# 3_5_2-_-V3_3-2023_10_27.net
KiCad netlist of a schematic drawn in Altium Designer
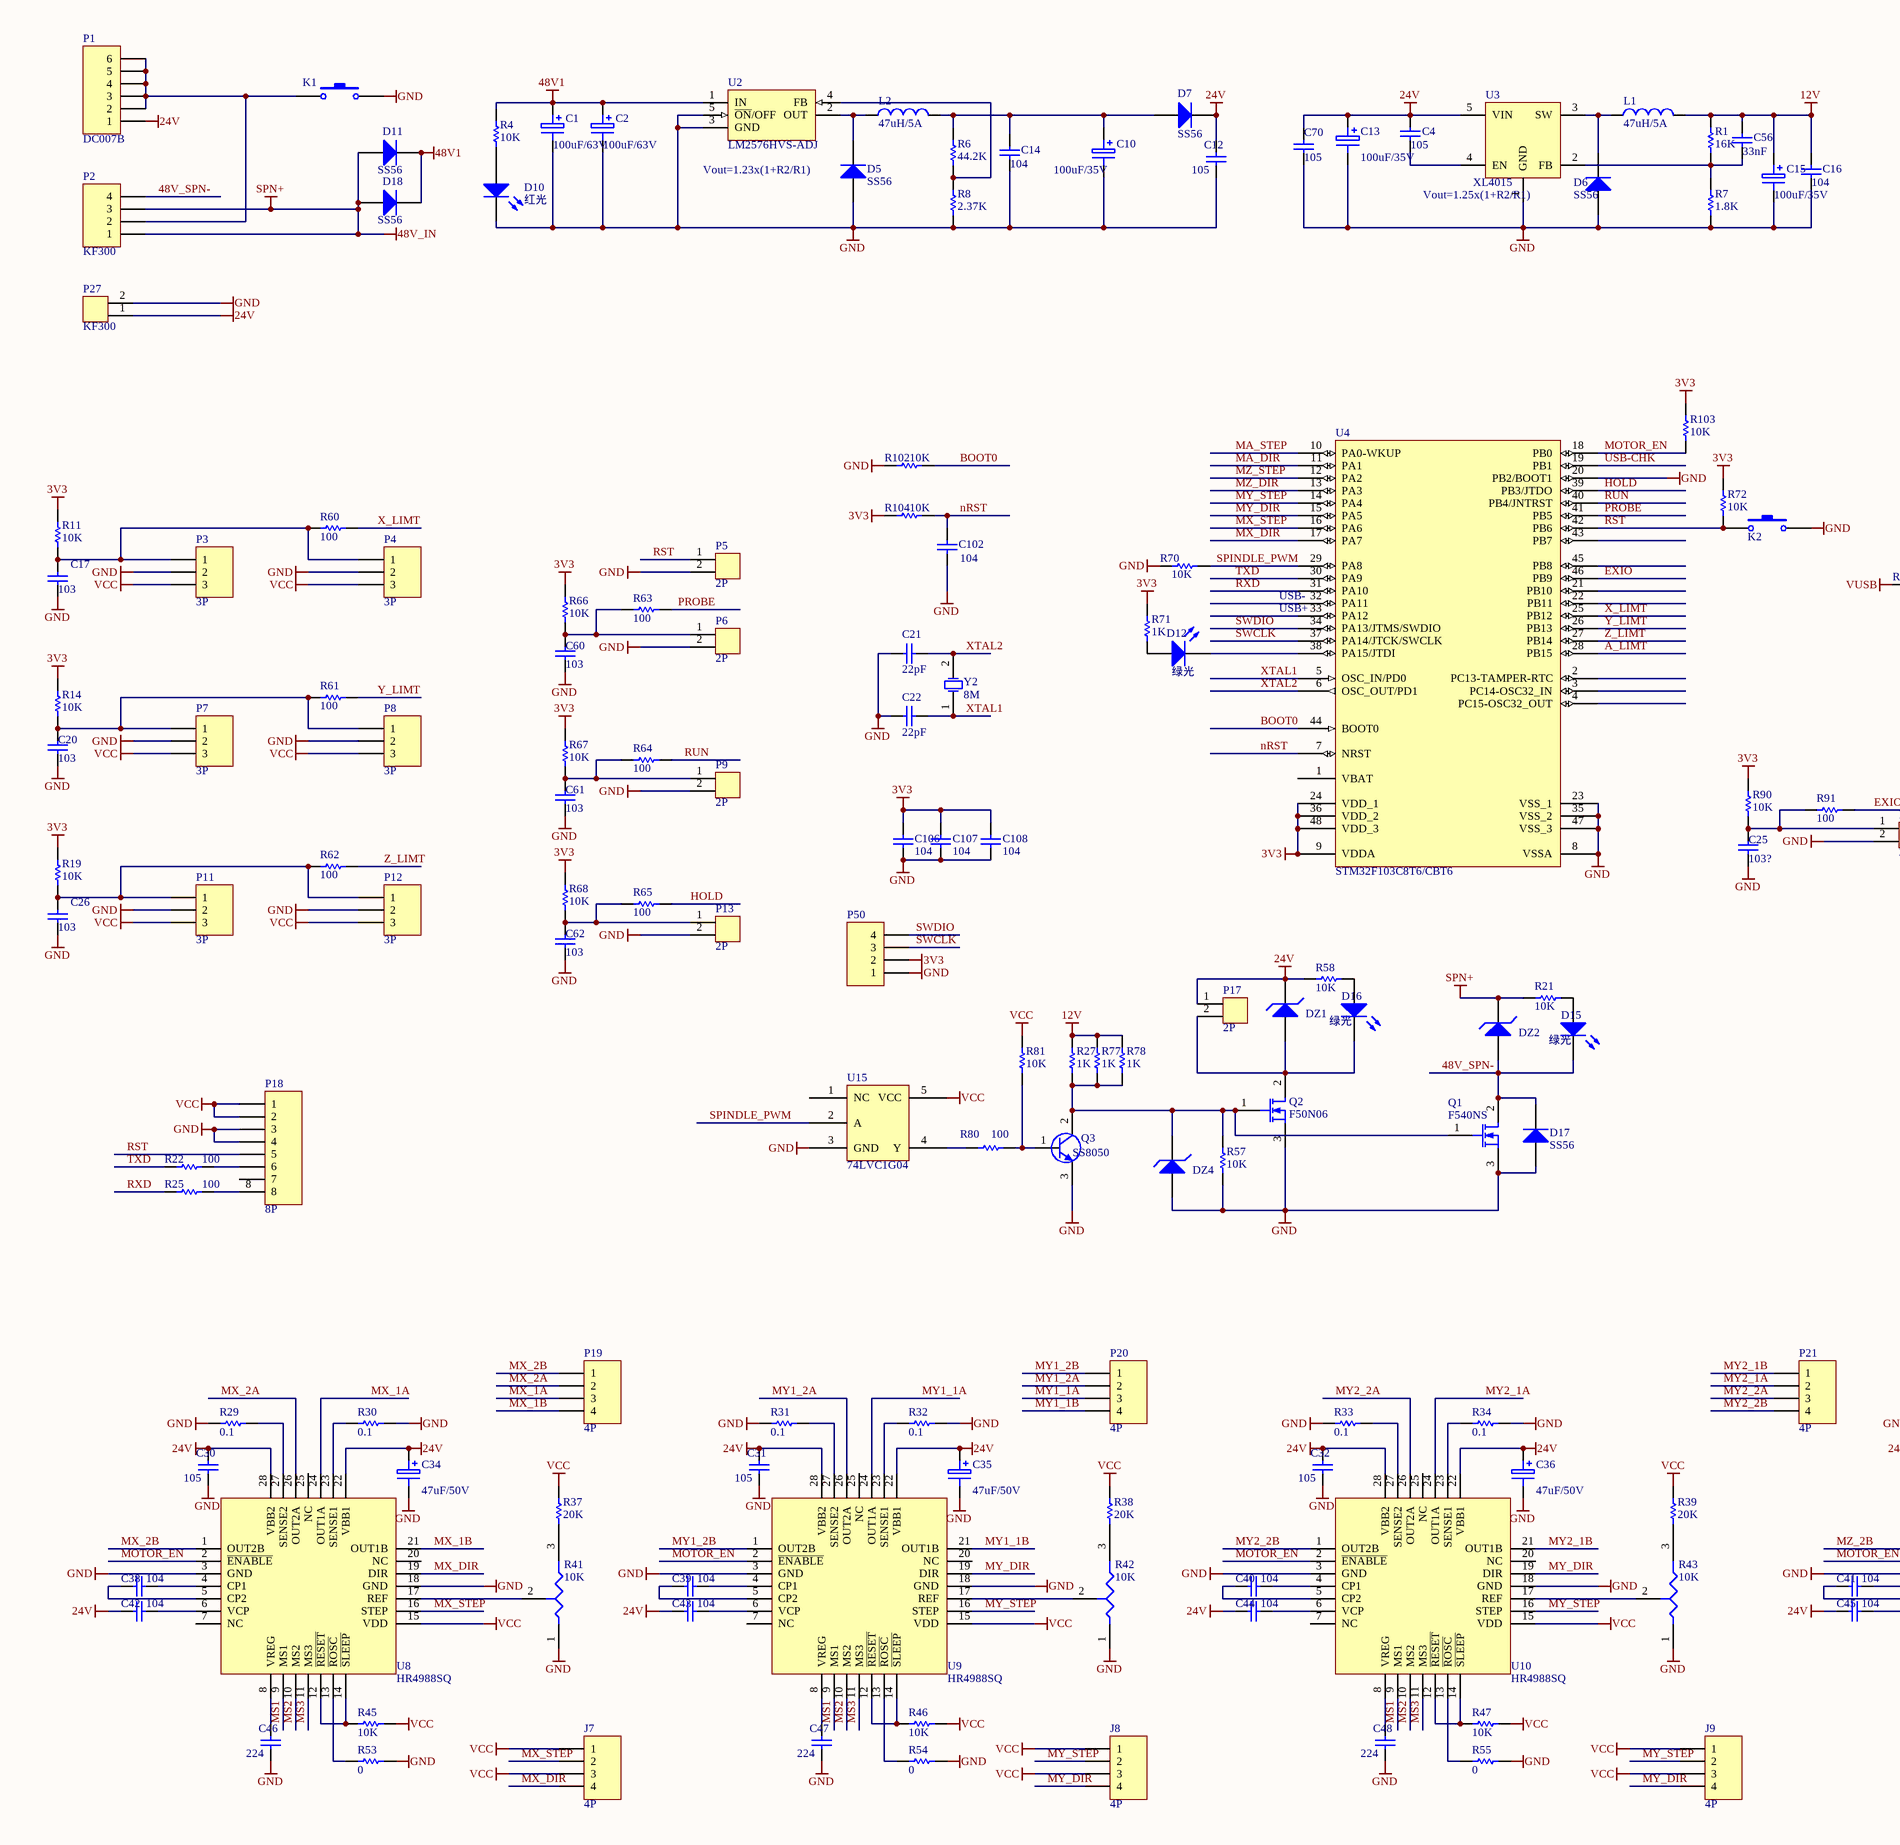
[diagram p0: 3轴5.2-原理图-V3.3-2023.10.27.SchDoc, left]
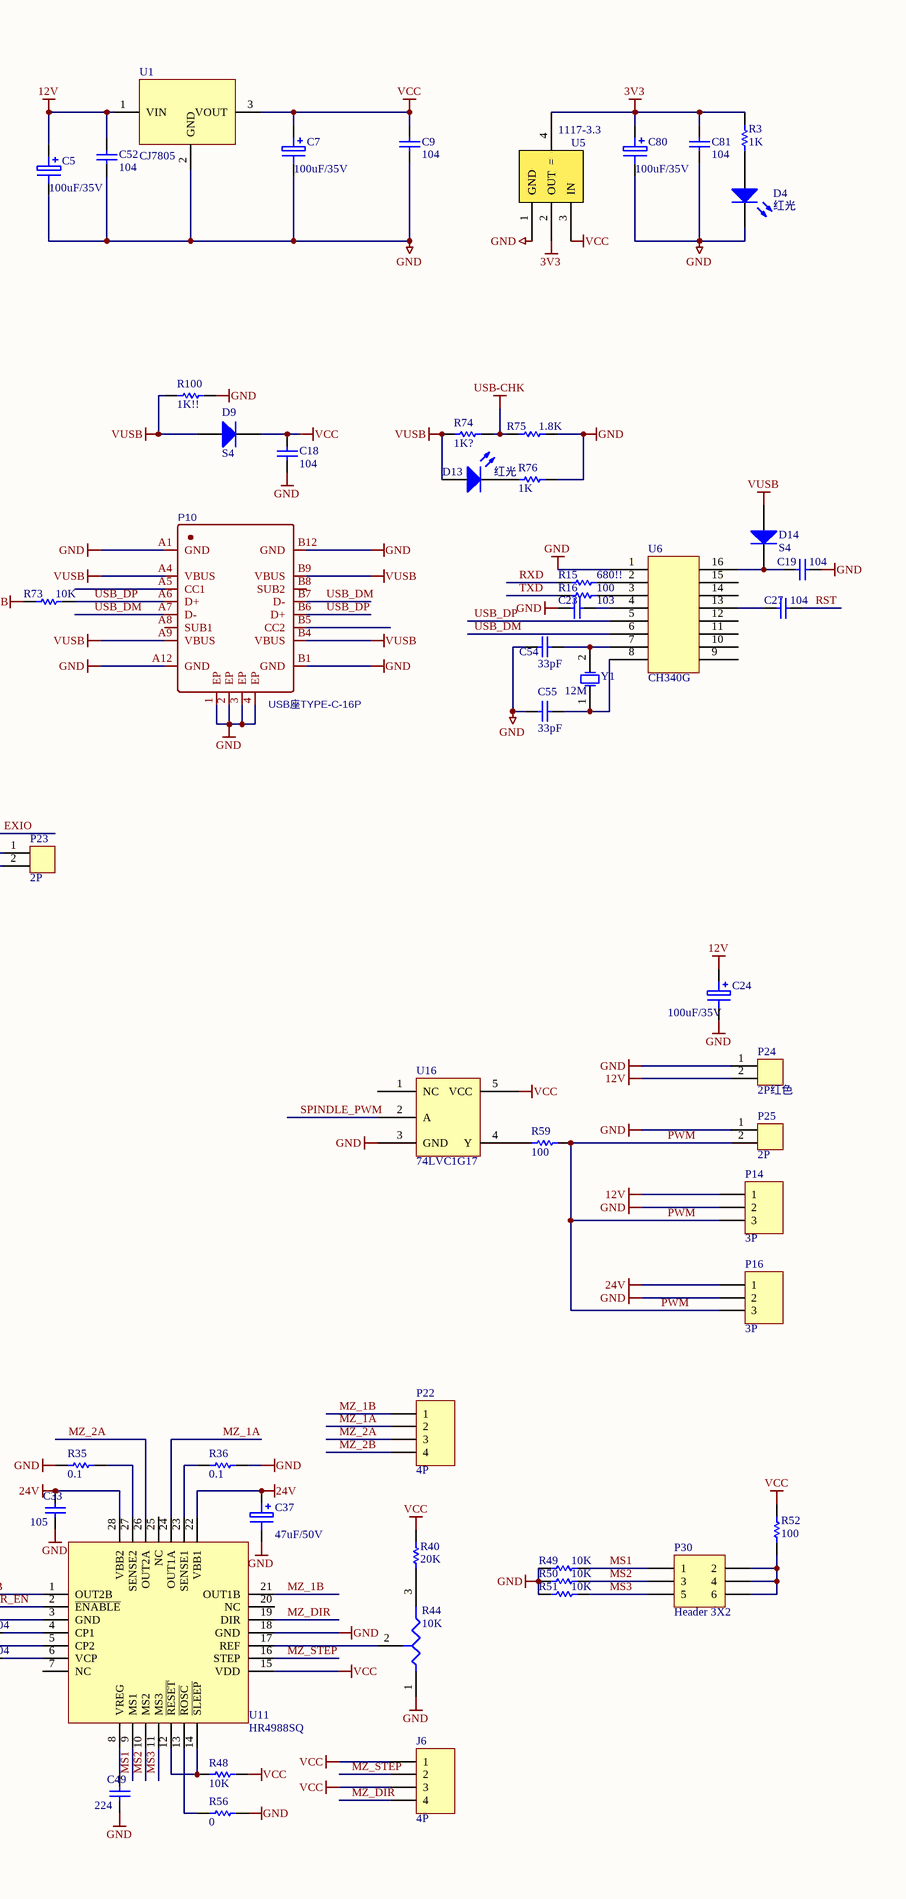
[diagram p1: 3轴5.2-原理图-V3.3-2023.10.27.SchDoc, right]

(export (version "E")
  (design (tool "Eeschema 10.0.6"))
  (components
    (comp (ref "C1") (value "100uF/63V") (footprint "电解电容贴片10x10") (libsource (lib "*") (part "ELECTRO1")))
    (comp (ref "C2") (value "100uF/63V") (footprint "电解电容贴片10x10") (libsource (lib "*") (part "ELECTRO1")))
    (comp (ref "C4") (value "105") (footprint "0805C") (libsource (lib "SCH封装库") (part "CAP")))
    (comp (ref "C5") (value "100uF/35V") (footprint "电解电容贴片6x6") (libsource (lib "*") (part "ELECTRO1")))
    (comp (ref "C7") (value "100uF/35V") (footprint "电解电容贴片6x6") (libsource (lib "*") (part "ELECTRO1")))
    (comp (ref "C9")
      (value "104")
      (footprint "0603C")
      (description "Capacitor (Semiconductor SIM Model)")
      (fields (field (name "PUBLISHER") "Altium Limited"))
      (libsource (lib "Miscellaneous Devices") (part "Cap Semi"))
    )
    (comp (ref "C10") (value "100uF/35V") (footprint "电解电容贴片6x6") (libsource (lib "*") (part "ELECTRO1")))
    (comp (ref "C12") (value "105") (footprint "0805C") (libsource (lib "SCH封装库") (part "CAP")))
    (comp (ref "C13") (value "100uF/35V") (footprint "电解电容贴片6x6") (libsource (lib "*") (part "ELECTRO1")))
    (comp (ref "C14") (value "104") (footprint "0603C") (libsource (lib "SCH封装库") (part "CAP")))
    (comp (ref "C15") (value "100uF/35V") (footprint "电解电容贴片6x6") (libsource (lib "*") (part "ELECTRO1")))
    (comp (ref "C16") (value "104") (footprint "0603C") (libsource (lib "SCH封装库") (part "CAP")))
    (comp (ref "C17") (value "103") (footprint "0603C") (libsource (lib "SCH封装库") (part "CAP")))
    (comp (ref "C18")
      (value "104")
      (footprint "0603C")
      (description "Capacitor (Semiconductor SIM Model)")
      (fields (field (name "PUBLISHER") "Altium Limited"))
      (libsource (lib "Miscellaneous Devices") (part "Cap Semi"))
    )
    (comp (ref "C19")
      (value "104")
      (footprint "0603C")
      (description "Capacitor (Semiconductor SIM Model)")
      (fields (field (name "PUBLISHER") "Altium Limited"))
      (libsource (lib "Miscellaneous Devices") (part "Cap Semi"))
    )
    (comp (ref "C20") (value "103") (footprint "0603C") (libsource (lib "SCH封装库") (part "CAP")))
    (comp (ref "C21")
      (value "22pF")
      (footprint "0603C")
      (description "Capacitor (Semiconductor SIM Model)")
      (fields (field (name "PUBLISHER") "Altium Limited"))
      (libsource (lib "Miscellaneous Devices") (part "Cap Semi"))
    )
    (comp (ref "C22")
      (value "22pF")
      (footprint "0603C")
      (description "Capacitor (Semiconductor SIM Model)")
      (fields (field (name "PUBLISHER") "Altium Limited"))
      (libsource (lib "Miscellaneous Devices") (part "Cap Semi"))
    )
    (comp (ref "C23")
      (value "103")
      (footprint "0603C")
      (description "Capacitor (Semiconductor SIM Model)")
      (fields (field (name "PUBLISHER") "Altium Limited"))
      (libsource (lib "Miscellaneous Devices") (part "Cap Semi"))
    )
    (comp (ref "C24") (value "100uF/35V") (footprint "电解电容贴片6x6") (libsource (lib "*") (part "ELECTRO1")))
    (comp (ref "C25") (value "103?") (footprint "0603C") (libsource (lib "SCH封装库") (part "CAP")))
    (comp (ref "C26") (value "103") (footprint "0603C") (libsource (lib "SCH封装库") (part "CAP")))
    (comp (ref "C27")
      (value "104")
      (footprint "0603C")
      (description "Capacitor (Semiconductor SIM Model)")
      (fields (field (name "PUBLISHER") "Altium Limited"))
      (libsource (lib "Miscellaneous Devices") (part "Cap Semi"))
    )
    (comp (ref "C30") (value "105") (footprint "0805C") (libsource (lib "SCH封装库") (part "CAP")))
    (comp (ref "C31") (value "105") (footprint "0805C") (libsource (lib "SCH封装库") (part "CAP")))
    (comp (ref "C32") (value "105") (footprint "0805C") (libsource (lib "SCH封装库") (part "CAP")))
    (comp (ref "C33") (value "105") (footprint "0805C") (libsource (lib "SCH封装库") (part "CAP")))
    (comp (ref "C34") (value "47uF/50V") (footprint "电解电容贴片6x6") (libsource (lib "*") (part "ELECTRO1")))
    (comp (ref "C35") (value "47uF/50V") (footprint "电解电容贴片6x6") (libsource (lib "*") (part "ELECTRO1")))
    (comp (ref "C36") (value "47uF/50V") (footprint "电解电容贴片6x6") (libsource (lib "*") (part "ELECTRO1")))
    (comp (ref "C37") (value "47uF/50V") (footprint "电解电容贴片6x6") (libsource (lib "*") (part "ELECTRO1")))
    (comp (ref "C38") (value "104") (footprint "0603C") (libsource (lib "SCH封装库") (part "CAP")))
    (comp (ref "C39") (value "104") (footprint "0603C") (libsource (lib "SCH封装库") (part "CAP")))
    (comp (ref "C40") (value "104") (footprint "0603C") (libsource (lib "SCH封装库") (part "CAP")))
    (comp (ref "C41") (value "104") (footprint "0603C") (libsource (lib "SCH封装库") (part "CAP")))
    (comp (ref "C42") (value "104") (footprint "0603C") (libsource (lib "SCH封装库") (part "CAP")))
    (comp (ref "C43") (value "104") (footprint "0603C") (libsource (lib "SCH封装库") (part "CAP")))
    (comp (ref "C44") (value "104") (footprint "0603C") (libsource (lib "SCH封装库") (part "CAP")))
    (comp (ref "C45") (value "104") (footprint "0603C") (libsource (lib "SCH封装库") (part "CAP")))
    (comp (ref "C46") (value "224") (footprint "0603C") (libsource (lib "SCH封装库") (part "CAP")))
    (comp (ref "C47") (value "224") (footprint "0603C") (libsource (lib "SCH封装库") (part "CAP")))
    (comp (ref "C48") (value "224") (footprint "0603C") (libsource (lib "SCH封装库") (part "CAP")))
    (comp (ref "C49") (value "224") (footprint "0603C") (libsource (lib "SCH封装库") (part "CAP")))
    (comp (ref "C52")
      (value "104")
      (footprint "0603C")
      (description "Capacitor (Semiconductor SIM Model)")
      (fields (field (name "PUBLISHER") "Altium Limited"))
      (libsource (lib "Miscellaneous Devices") (part "Cap Semi"))
    )
    (comp (ref "C54")
      (value "33pF")
      (footprint "0603C")
      (description "Capacitor (Semiconductor SIM Model)")
      (fields (field (name "PUBLISHER") "Altium Limited"))
      (libsource (lib "Miscellaneous Devices") (part "Cap Semi"))
    )
    (comp (ref "C55")
      (value "33pF")
      (footprint "0603C")
      (description "Capacitor (Semiconductor SIM Model)")
      (fields (field (name "PUBLISHER") "Altium Limited"))
      (libsource (lib "Miscellaneous Devices") (part "Cap Semi"))
    )
    (comp (ref "C56") (value "33nF") (footprint "0603C") (libsource (lib "SCH封装库") (part "CAP")))
    (comp (ref "C60") (value "103") (footprint "0603C") (libsource (lib "SCH封装库") (part "CAP")))
    (comp (ref "C61") (value "103") (footprint "0603C") (libsource (lib "SCH封装库") (part "CAP")))
    (comp (ref "C62") (value "103") (footprint "0603C") (libsource (lib "SCH封装库") (part "CAP")))
    (comp (ref "C70") (value "105") (footprint "0805C") (libsource (lib "SCH封装库") (part "CAP")))
    (comp (ref "C80") (value "100uF/35V") (footprint "电解电容贴片6x6") (libsource (lib "*") (part "ELECTRO1")))
    (comp (ref "C81")
      (value "104")
      (footprint "0603C")
      (description "Capacitor (Semiconductor SIM Model)")
      (fields (field (name "PUBLISHER") "Altium Limited"))
      (libsource (lib "Miscellaneous Devices") (part "Cap Semi"))
    )
    (comp (ref "C102")
      (value "104")
      (footprint "0603C")
      (description "Capacitor (Semiconductor SIM Model)")
      (fields (field (name "PUBLISHER") "Altium Limited"))
      (libsource (lib "Miscellaneous Devices") (part "Cap Semi"))
    )
    (comp (ref "C106") (value "104") (footprint "0603C") (libsource (lib "SCH封装库") (part "CAP")))
    (comp (ref "C107") (value "104") (footprint "0603C") (libsource (lib "SCH封装库") (part "CAP")))
    (comp (ref "C108") (value "104") (footprint "0603C") (libsource (lib "SCH封装库") (part "CAP")))
    (comp (ref "D4") (value "红光") (footprint "0603LED") (libsource (lib "SCH封装库") (part "LED")))
    (comp (ref "D5") (value "SS56") (footprint "SMA") (libsource (lib "SCH封装库") (part "1N4148")))
    (comp (ref "D6") (value "SS56") (footprint "SMA") (libsource (lib "SCH封装库") (part "1N4148")))
    (comp (ref "D7") (value "SS56") (footprint "SMA") (libsource (lib "SCH封装库") (part "1N4148")))
    (comp (ref "D9") (value "S4") (footprint "SOD-123") (libsource (lib "SCH封装库") (part "1N4148")))
    (comp (ref "D10") (value "红光") (footprint "0603LED") (libsource (lib "SCH封装库") (part "LED")))
    (comp (ref "D11") (value "SS56") (footprint "SMA") (libsource (lib "SCH封装库") (part "1N4148")))
    (comp (ref "D12") (value "绿光") (footprint "0603LED") (libsource (lib "SCH封装库") (part "LED")))
    (comp (ref "D13") (value "红光") (footprint "0603LED") (libsource (lib "SCH封装库") (part "LED")))
    (comp (ref "D14") (value "S4") (footprint "SOD-123") (libsource (lib "SCH封装库") (part "1N4148")))
    (comp (ref "D15") (value "绿光") (footprint "0603LED") (libsource (lib "SCH封装库") (part "LED")))
    (comp (ref "D16") (value "绿光") (footprint "0603LED") (libsource (lib "SCH封装库") (part "LED")))
    (comp (ref "D17") (value "SS56") (footprint "SMA") (libsource (lib "SCH封装库") (part "1N4148")))
    (comp (ref "D18") (value "SS56") (footprint "SMA") (libsource (lib "SCH封装库") (part "1N4148")))
    (comp (ref "DZ1") (value "快恢复二极管RS2M") (footprint "SMC") (libsource (lib "SCH封装库") (part "稳压二极管")))
    (comp (ref "DZ2") (value "快恢复二极管RS2M") (footprint "SMC") (libsource (lib "SCH封装库") (part "稳压二极管")))
    (comp (ref "DZ4") (value "稳压二极管SMAZ10V") (footprint "SMA") (libsource (lib "SCH封装库") (part "稳压二极管")))
    (comp (ref "J6") (value "4P") (footprint "SIP4") (libsource (lib "SCH封装库") (part "4P")))
    (comp (ref "J7") (value "4P") (footprint "SIP4") (libsource (lib "SCH封装库") (part "4P")))
    (comp (ref "J8") (value "4P") (footprint "SIP4") (libsource (lib "SCH封装库") (part "4P")))
    (comp (ref "J9") (value "4P") (footprint "SIP4") (libsource (lib "SCH封装库") (part "4P")))
    (comp (ref "K1") (value "按键") (footprint "船型开关KCD1-101") (libsource (lib "SCH封装库") (part "按键")))
    (comp (ref "K2") (value "按键") (footprint "按键6x6贴片") (libsource (lib "SCH封装库") (part "按键")))
    (comp (ref "L1")
      (value "47uH/5A")
      (footprint "电感贴片12x12")
      (description "Inductor")
      (fields (field (name "PUBLISHER") "Altium Limited"))
      (libsource (lib "SCH封装库") (part "Inductor"))
    )
    (comp (ref "L2")
      (value "47uH/5A")
      (footprint "电感贴片12x12")
      (description "Inductor")
      (fields (field (name "PUBLISHER") "Altium Limited"))
      (libsource (lib "SCH封装库") (part "Inductor"))
    )
    (comp (ref "P1") (value "DC007B") (footprint "DC007B") (libsource (lib "SCH封装库") (part "6P")))
    (comp (ref "P2") (value "KF300") (footprint "直插座4P-KF300") (libsource (lib "") (part "4P_1")))
    (comp (ref "P3") (value "3P") (footprint "HDR1X3_CON") (libsource (lib "SCH封装库") (part "3P")))
    (comp (ref "P4") (value "3P") (footprint "HDR1X3_CON") (libsource (lib "SCH封装库") (part "3P")))
    (comp (ref "P5") (value "2P") (footprint "HDR1X2_CON") (libsource (lib "") (part "2P_1")))
    (comp (ref "P6") (value "2P") (footprint "HDR1X2_CON") (libsource (lib "") (part "2P_1")))
    (comp (ref "P7") (value "3P") (footprint "HDR1X3_CON") (libsource (lib "SCH封装库") (part "3P")))
    (comp (ref "P8") (value "3P") (footprint "HDR1X3_CON") (libsource (lib "SCH封装库") (part "3P")))
    (comp (ref "P9") (value "2P") (footprint "HDR1X2_CON") (libsource (lib "") (part "2P_1")))
    (comp (ref "P10")
      (value "USB座TYPE-C-16P")
      (footprint "USB-TYPE-C-16P")
      (fields
        (field (name "BOM_SUPPLIER PART") "C709358")
        (field (name "BOM_MANUFACTURER PART") "KH-TYPE-C-16P-T")
        (field (name "CONTRIBUTOR") "LCSC")
      )
      (libsource (lib "SCH封装库") (part "USB座TYPE-C-16P"))
    )
    (comp (ref "P11") (value "3P") (footprint "HDR1X3_CON") (libsource (lib "SCH封装库") (part "3P")))
    (comp (ref "P12") (value "3P") (footprint "HDR1X3_CON") (libsource (lib "SCH封装库") (part "3P")))
    (comp (ref "P13") (value "2P") (footprint "HDR1X2_CON") (libsource (lib "") (part "2P_1")))
    (comp (ref "P14") (value "3P") (footprint "HDR1X3_CON") (libsource (lib "SCH封装库") (part "3P")))
    (comp (ref "P16") (value "3P") (footprint "HDR1X3_CON") (libsource (lib "SCH封装库") (part "3P")))
    (comp (ref "P17") (value "2P") (footprint "VH3.96-2P直插座") (libsource (lib "") (part "2P_1")))
    (comp (ref "P18") (value "8P") (footprint "IDC8") (libsource (lib "SCH封装库") (part "8P")))
    (comp (ref "P19") (value "4P") (footprint "HDR1X4_CON") (libsource (lib "SCH封装库") (part "4P")))
    (comp (ref "P20") (value "4P") (footprint "HDR1X4_CON") (libsource (lib "SCH封装库") (part "4P")))
    (comp (ref "P21") (value "4P") (footprint "HDR1X4_CON") (libsource (lib "SCH封装库") (part "4P")))
    (comp (ref "P22") (value "4P") (footprint "HDR1X4_CON") (libsource (lib "SCH封装库") (part "4P")))
    (comp (ref "P23") (value "2P") (footprint "HDR1X2_CON") (libsource (lib "") (part "2P_1")))
    (comp (ref "P24") (value "2P红色") (footprint "HDR1X2_CON") (libsource (lib "") (part "2P_1")))
    (comp (ref "P25") (value "2P") (footprint "HDR1X2_CON") (libsource (lib "") (part "2P_1")))
    (comp (ref "P27") (value "KF300") (footprint "直插座2P-KF300") (libsource (lib "SCH封装库") (part "2P")))
    (comp (ref "P30")
      (value "Header 3X2")
      (footprint "HDR2X3")
      (description "Header, 3-Pin, Dual row")
      (fields (field (name "PUBLISHER") "Altium Limited"))
      (libsource (lib "Miscellaneous Connectors") (part "Header 3X2"))
    )
    (comp (ref "P50") (value "~") (footprint "SIP4") (libsource (lib "") (part "4P_1")))
    (comp (ref "Q1")
      (value "F540NS")
      (footprint "TO-263-2")
      (description "N-Channel MOSFET")
      (fields (field (name "PUBLISHER") "Altium Limited"))
      (libsource (lib "SCH封装库") (part "MOSFET-N"))
    )
    (comp (ref "Q2")
      (value "F50N06")
      (footprint "TO-252")
      (description "N-Channel MOSFET")
      (fields (field (name "PUBLISHER") "Altium Limited"))
      (libsource (lib "SCH封装库") (part "MOSFET-N"))
    )
    (comp (ref "Q3")
      (value "SS8050")
      (footprint "SOT-23")
      (fields (field (name "PUBLISHER") "Altium Limited"))
      (libsource (lib "SCH封装库") (part "NPN"))
    )
    (comp (ref "R1")
      (value "16K")
      (footprint "0603R")
      (description "Resistor")
      (fields (field (name "PUBLISHER") "Altium Limited"))
      (libsource (lib "SCH封装库") (part "RES"))
    )
    (comp (ref "R3")
      (value "1K")
      (footprint "0603R")
      (description "Resistor")
      (fields (field (name "PUBLISHER") "Altium Limited"))
      (libsource (lib "SCH封装库") (part "RES"))
    )
    (comp (ref "R4")
      (value "10K")
      (footprint "0603R")
      (description "Resistor")
      (fields (field (name "PUBLISHER") "Altium Limited"))
      (libsource (lib "SCH封装库") (part "RES"))
    )
    (comp (ref "R6")
      (value "44.2K")
      (footprint "0603R")
      (description "Resistor")
      (fields (field (name "PUBLISHER") "Altium Limited"))
      (libsource (lib "SCH封装库") (part "RES"))
    )
    (comp (ref "R7")
      (value "1.8K")
      (footprint "0603R")
      (description "Resistor")
      (fields (field (name "PUBLISHER") "Altium Limited"))
      (libsource (lib "SCH封装库") (part "RES"))
    )
    (comp (ref "R8")
      (value "2.37K")
      (footprint "0603R")
      (description "Resistor")
      (fields (field (name "PUBLISHER") "Altium Limited"))
      (libsource (lib "SCH封装库") (part "RES"))
    )
    (comp (ref "R11")
      (value "10K")
      (footprint "0603R")
      (description "Resistor")
      (fields (field (name "PUBLISHER") "Altium Limited"))
      (libsource (lib "SCH封装库") (part "RES"))
    )
    (comp (ref "R14")
      (value "10K")
      (footprint "0603R")
      (description "Resistor")
      (fields (field (name "PUBLISHER") "Altium Limited"))
      (libsource (lib "SCH封装库") (part "RES"))
    )
    (comp (ref "R15")
      (value "680!!")
      (footprint "0603R")
      (description "Resistor")
      (fields (field (name "PUBLISHER") "Altium Limited"))
      (libsource (lib "SCH封装库") (part "RES"))
    )
    (comp (ref "R16")
      (value "100")
      (footprint "0603R")
      (description "Resistor")
      (fields (field (name "PUBLISHER") "Altium Limited"))
      (libsource (lib "SCH封装库") (part "RES"))
    )
    (comp (ref "R19")
      (value "10K")
      (footprint "0603R")
      (description "Resistor")
      (fields (field (name "PUBLISHER") "Altium Limited"))
      (libsource (lib "SCH封装库") (part "RES"))
    )
    (comp (ref "R21")
      (value "10K")
      (footprint "0603R")
      (description "Resistor")
      (fields (field (name "PUBLISHER") "Altium Limited"))
      (libsource (lib "SCH封装库") (part "RES"))
    )
    (comp (ref "R22")
      (value "100")
      (footprint "0603R")
      (description "Resistor")
      (fields (field (name "PUBLISHER") "Altium Limited"))
      (libsource (lib "SCH封装库") (part "RES"))
    )
    (comp (ref "R25")
      (value "100")
      (footprint "0603R")
      (description "Resistor")
      (fields (field (name "PUBLISHER") "Altium Limited"))
      (libsource (lib "SCH封装库") (part "RES"))
    )
    (comp (ref "R27")
      (value "1K")
      (footprint "0603R")
      (description "Resistor")
      (fields (field (name "PUBLISHER") "Altium Limited"))
      (libsource (lib "SCH封装库") (part "RES"))
    )
    (comp (ref "R29")
      (value "0.1")
      (footprint "0805R")
      (description "Resistor")
      (fields (field (name "PUBLISHER") "Altium Limited"))
      (libsource (lib "SCH封装库") (part "RES"))
    )
    (comp (ref "R30")
      (value "0.1")
      (footprint "0805R")
      (description "Resistor")
      (fields (field (name "PUBLISHER") "Altium Limited"))
      (libsource (lib "SCH封装库") (part "RES"))
    )
    (comp (ref "R31")
      (value "0.1")
      (footprint "0805R")
      (description "Resistor")
      (fields (field (name "PUBLISHER") "Altium Limited"))
      (libsource (lib "SCH封装库") (part "RES"))
    )
    (comp (ref "R32")
      (value "0.1")
      (footprint "0805R")
      (description "Resistor")
      (fields (field (name "PUBLISHER") "Altium Limited"))
      (libsource (lib "SCH封装库") (part "RES"))
    )
    (comp (ref "R33")
      (value "0.1")
      (footprint "0805R")
      (description "Resistor")
      (fields (field (name "PUBLISHER") "Altium Limited"))
      (libsource (lib "SCH封装库") (part "RES"))
    )
    (comp (ref "R34")
      (value "0.1")
      (footprint "0805R")
      (description "Resistor")
      (fields (field (name "PUBLISHER") "Altium Limited"))
      (libsource (lib "SCH封装库") (part "RES"))
    )
    (comp (ref "R35")
      (value "0.1")
      (footprint "0805R")
      (description "Resistor")
      (fields (field (name "PUBLISHER") "Altium Limited"))
      (libsource (lib "SCH封装库") (part "RES"))
    )
    (comp (ref "R36")
      (value "0.1")
      (footprint "0805R")
      (description "Resistor")
      (fields (field (name "PUBLISHER") "Altium Limited"))
      (libsource (lib "SCH封装库") (part "RES"))
    )
    (comp (ref "R37")
      (value "20K")
      (footprint "0603R")
      (description "Resistor")
      (fields (field (name "PUBLISHER") "Altium Limited"))
      (libsource (lib "SCH封装库") (part "RES"))
    )
    (comp (ref "R38")
      (value "20K")
      (footprint "0603R")
      (description "Resistor")
      (fields (field (name "PUBLISHER") "Altium Limited"))
      (libsource (lib "SCH封装库") (part "RES"))
    )
    (comp (ref "R39")
      (value "20K")
      (footprint "0603R")
      (description "Resistor")
      (fields (field (name "PUBLISHER") "Altium Limited"))
      (libsource (lib "SCH封装库") (part "RES"))
    )
    (comp (ref "R40")
      (value "20K")
      (footprint "0603R")
      (description "Resistor")
      (fields (field (name "PUBLISHER") "Altium Limited"))
      (libsource (lib "SCH封装库") (part "RES"))
    )
    (comp (ref "R41") (value "10K") (footprint "松下贴片电位器3x3") (libsource (lib "SCH封装库") (part "电位器")))
    (comp (ref "R42") (value "10K") (footprint "松下贴片电位器3x3") (libsource (lib "SCH封装库") (part "电位器")))
    (comp (ref "R43") (value "10K") (footprint "松下贴片电位器3x3") (libsource (lib "SCH封装库") (part "电位器")))
    (comp (ref "R44") (value "10K") (footprint "松下贴片电位器3x3") (libsource (lib "SCH封装库") (part "电位器")))
    (comp (ref "R45")
      (value "10K")
      (footprint "0603R")
      (description "Resistor")
      (fields (field (name "PUBLISHER") "Altium Limited"))
      (libsource (lib "SCH封装库") (part "RES"))
    )
    (comp (ref "R46")
      (value "10K")
      (footprint "0603R")
      (description "Resistor")
      (fields (field (name "PUBLISHER") "Altium Limited"))
      (libsource (lib "SCH封装库") (part "RES"))
    )
    (comp (ref "R47")
      (value "10K")
      (footprint "0603R")
      (description "Resistor")
      (fields (field (name "PUBLISHER") "Altium Limited"))
      (libsource (lib "SCH封装库") (part "RES"))
    )
    (comp (ref "R48")
      (value "10K")
      (footprint "0603R")
      (description "Resistor")
      (fields (field (name "PUBLISHER") "Altium Limited"))
      (libsource (lib "SCH封装库") (part "RES"))
    )
    (comp (ref "R49")
      (value "10K")
      (footprint "0603R")
      (description "Resistor")
      (fields (field (name "PUBLISHER") "Altium Limited"))
      (libsource (lib "SCH封装库") (part "RES"))
    )
    (comp (ref "R50")
      (value "10K")
      (footprint "0603R")
      (description "Resistor")
      (fields (field (name "PUBLISHER") "Altium Limited"))
      (libsource (lib "SCH封装库") (part "RES"))
    )
    (comp (ref "R51")
      (value "10K")
      (footprint "0603R")
      (description "Resistor")
      (fields (field (name "PUBLISHER") "Altium Limited"))
      (libsource (lib "SCH封装库") (part "RES"))
    )
    (comp (ref "R52")
      (value "100")
      (footprint "0603R")
      (description "Resistor")
      (fields (field (name "PUBLISHER") "Altium Limited"))
      (libsource (lib "SCH封装库") (part "RES"))
    )
    (comp (ref "R53")
      (value "0")
      (footprint "0603R")
      (description "Resistor")
      (fields (field (name "PUBLISHER") "Altium Limited"))
      (libsource (lib "SCH封装库") (part "RES"))
    )
    (comp (ref "R54")
      (value "0")
      (footprint "0603R")
      (description "Resistor")
      (fields (field (name "PUBLISHER") "Altium Limited"))
      (libsource (lib "SCH封装库") (part "RES"))
    )
    (comp (ref "R55")
      (value "0")
      (footprint "0603R")
      (description "Resistor")
      (fields (field (name "PUBLISHER") "Altium Limited"))
      (libsource (lib "SCH封装库") (part "RES"))
    )
    (comp (ref "R56")
      (value "0")
      (footprint "0603R")
      (description "Resistor")
      (fields (field (name "PUBLISHER") "Altium Limited"))
      (libsource (lib "SCH封装库") (part "RES"))
    )
    (comp (ref "R57")
      (value "10K")
      (footprint "0603R")
      (description "Resistor")
      (fields (field (name "PUBLISHER") "Altium Limited"))
      (libsource (lib "SCH封装库") (part "RES"))
    )
    (comp (ref "R58")
      (value "10K")
      (footprint "0603R")
      (description "Resistor")
      (fields (field (name "PUBLISHER") "Altium Limited"))
      (libsource (lib "SCH封装库") (part "RES"))
    )
    (comp (ref "R59")
      (value "100")
      (footprint "0603R")
      (description "Resistor")
      (fields (field (name "PUBLISHER") "Altium Limited"))
      (libsource (lib "SCH封装库") (part "RES"))
    )
    (comp (ref "R60")
      (value "100")
      (footprint "0603R")
      (description "Resistor")
      (fields (field (name "PUBLISHER") "Altium Limited"))
      (libsource (lib "SCH封装库") (part "RES"))
    )
    (comp (ref "R61")
      (value "100")
      (footprint "0603R")
      (description "Resistor")
      (fields (field (name "PUBLISHER") "Altium Limited"))
      (libsource (lib "SCH封装库") (part "RES"))
    )
    (comp (ref "R62")
      (value "100")
      (footprint "0603R")
      (description "Resistor")
      (fields (field (name "PUBLISHER") "Altium Limited"))
      (libsource (lib "SCH封装库") (part "RES"))
    )
    (comp (ref "R63")
      (value "100")
      (footprint "0603R")
      (description "Resistor")
      (fields (field (name "PUBLISHER") "Altium Limited"))
      (libsource (lib "SCH封装库") (part "RES"))
    )
    (comp (ref "R64")
      (value "100")
      (footprint "0603R")
      (description "Resistor")
      (fields (field (name "PUBLISHER") "Altium Limited"))
      (libsource (lib "SCH封装库") (part "RES"))
    )
    (comp (ref "R65")
      (value "100")
      (footprint "0603R")
      (description "Resistor")
      (fields (field (name "PUBLISHER") "Altium Limited"))
      (libsource (lib "SCH封装库") (part "RES"))
    )
    (comp (ref "R66")
      (value "10K")
      (footprint "0603R")
      (description "Resistor")
      (fields (field (name "PUBLISHER") "Altium Limited"))
      (libsource (lib "SCH封装库") (part "RES"))
    )
    (comp (ref "R67")
      (value "10K")
      (footprint "0603R")
      (description "Resistor")
      (fields (field (name "PUBLISHER") "Altium Limited"))
      (libsource (lib "SCH封装库") (part "RES"))
    )
    (comp (ref "R68")
      (value "10K")
      (footprint "0603R")
      (description "Resistor")
      (fields (field (name "PUBLISHER") "Altium Limited"))
      (libsource (lib "SCH封装库") (part "RES"))
    )
    (comp (ref "R70")
      (value "10K")
      (footprint "0603R")
      (description "Resistor")
      (fields (field (name "PUBLISHER") "Altium Limited"))
      (libsource (lib "SCH封装库") (part "RES"))
    )
    (comp (ref "R71")
      (value "1K")
      (footprint "0603R")
      (description "Resistor")
      (fields (field (name "PUBLISHER") "Altium Limited"))
      (libsource (lib "SCH封装库") (part "RES"))
    )
    (comp (ref "R72")
      (value "10K")
      (footprint "0603R")
      (description "Resistor")
      (fields (field (name "PUBLISHER") "Altium Limited"))
      (libsource (lib "SCH封装库") (part "RES"))
    )
    (comp (ref "R73")
      (value "10K")
      (footprint "0603R")
      (description "Resistor")
      (fields (field (name "PUBLISHER") "Altium Limited"))
      (libsource (lib "SCH封装库") (part "RES"))
    )
    (comp (ref "R74")
      (value "1K?")
      (footprint "0603R")
      (description "Resistor")
      (fields (field (name "PUBLISHER") "Altium Limited"))
      (libsource (lib "SCH封装库") (part "RES"))
    )
    (comp (ref "R75")
      (value "1.8K")
      (footprint "0603R")
      (description "Resistor")
      (fields (field (name "PUBLISHER") "Altium Limited"))
      (libsource (lib "SCH封装库") (part "RES"))
    )
    (comp (ref "R76")
      (value "1K")
      (footprint "0603R")
      (description "Resistor")
      (fields (field (name "PUBLISHER") "Altium Limited"))
      (libsource (lib "SCH封装库") (part "RES"))
    )
    (comp (ref "R77")
      (value "1K")
      (footprint "0603R")
      (description "Resistor")
      (fields (field (name "PUBLISHER") "Altium Limited"))
      (libsource (lib "SCH封装库") (part "RES"))
    )
    (comp (ref "R78")
      (value "1K")
      (footprint "0603R")
      (description "Resistor")
      (fields (field (name "PUBLISHER") "Altium Limited"))
      (libsource (lib "SCH封装库") (part "RES"))
    )
    (comp (ref "R80")
      (value "100")
      (footprint "0603R")
      (description "Resistor")
      (fields (field (name "PUBLISHER") "Altium Limited"))
      (libsource (lib "SCH封装库") (part "RES"))
    )
    (comp (ref "R81")
      (value "10K")
      (footprint "0603R")
      (description "Resistor")
      (fields (field (name "PUBLISHER") "Altium Limited"))
      (libsource (lib "SCH封装库") (part "RES"))
    )
    (comp (ref "R90")
      (value "10K")
      (footprint "0603R")
      (description "Resistor")
      (fields (field (name "PUBLISHER") "Altium Limited"))
      (libsource (lib "SCH封装库") (part "RES"))
    )
    (comp (ref "R91")
      (value "100")
      (footprint "0603R")
      (description "Resistor")
      (fields (field (name "PUBLISHER") "Altium Limited"))
      (libsource (lib "SCH封装库") (part "RES"))
    )
    (comp (ref "R100")
      (value "1K!!")
      (footprint "0603R")
      (description "Resistor")
      (fields (field (name "PUBLISHER") "Altium Limited"))
      (libsource (lib "SCH封装库") (part "RES"))
    )
    (comp (ref "R102")
      (value "10K")
      (footprint "0603R")
      (description "Resistor")
      (fields (field (name "Comment") "10k") (field (name "PUBLISHER") "Altium Limited"))
      (libsource (lib "SCH封装库") (part "RES"))
    )
    (comp (ref "R103")
      (value "10K")
      (footprint "0603R")
      (description "Resistor")
      (fields (field (name "PUBLISHER") "Altium Limited"))
      (libsource (lib "SCH封装库") (part "RES"))
    )
    (comp (ref "R104")
      (value "10K")
      (footprint "0603R")
      (description "Resistor")
      (fields (field (name "Comment") "10k") (field (name "PUBLISHER") "Altium Limited"))
      (libsource (lib "SCH封装库") (part "RES"))
    )
    (comp (ref "U1") (value "CJ7805") (footprint "TO-263-2") (libsource (lib "SCH封装库") (part "7805")))
    (comp (ref "U2")
      (value "LM2576HVS-ADJ")
      (footprint "TO-263")
      (description "Simple Switcher 3A Step Down Voltage Regulator")
      (fields (field (name "PUBLISHER") "Altium Limited"))
      (libsource (lib "NSC Power Mgt Switching Regulator") (part "LM2576S-5.0"))
    )
    (comp (ref "U3") (value "XL4015") (footprint "TO-263") (libsource (lib "SCH封装库") (part "XL4005")))
    (comp (ref "U4")
      (value "STM32F103C8T6/CBT6")
      (footprint "LQFP48")
      (description "STM32 ARM-based 32-bit MCU with 32 Kbytes Flash, 48-pin LQFP, Industrial Temperature")
      (fields (field (name "PUBLISHER") "*"))
      (libsource (lib "ST Microcontroller 32-Bit STM32 SCH") (part "STM32F103C6T6"))
    )
    (comp (ref "U5") (value "1117-3.3") (footprint "SOT-223") (libsource (lib "Party600") (part "LM1117")))
    (comp (ref "U6") (value "CH340G") (footprint "SOP16") (libsource (lib "SCH封装库") (part "DIP16")))
    (comp (ref "U8") (value "HR4988SQ") (footprint "QFN28") (libsource (lib "SCH封装库") (part "HR4988")))
    (comp (ref "U9") (value "HR4988SQ") (footprint "QFN28") (libsource (lib "SCH封装库") (part "HR4988")))
    (comp (ref "U10") (value "HR4988SQ") (footprint "QFN28") (libsource (lib "SCH封装库") (part "HR4988")))
    (comp (ref "U11") (value "HR4988SQ") (footprint "QFN28") (libsource (lib "SCH封装库") (part "HR4988")))
    (comp (ref "U15")
      (value "74LVC1G04")
      (footprint "SOT-23-5")
      (libsource (lib "SCH封装库") (part "74LVC1G17"))
    )
    (comp (ref "U16")
      (value "74LVC1G17")
      (footprint "SOT-23-5")
      (libsource (lib "SCH封装库") (part "74LVC1G17"))
    )
    (comp (ref "Y1")
      (value "12M")
      (footprint "晶振贴片49SSMD")
      (description "Crystal Oscillator")
      (fields (field (name "PUBLISHER") "Altium Limited"))
      (libsource (lib "Miscellaneous Devices") (part "XTAL"))
    )
    (comp (ref "Y2")
      (value "8M")
      (footprint "晶振贴片")
      (description "Crystal Oscillator")
      (fields (field (name "PUBLISHER") "Altium Limited"))
      (libsource (lib "Miscellaneous Devices") (part "XTAL"))
    )
  )
  (nets
    (net (code "1") (name "/48V_SPN-") (class "Default")
      (node (ref "D15") (pin "2") (pinfunction "2_2") (pintype "passive"))
      (node (ref "D17") (pin "2") (pinfunction "2_2") (pintype "passive"))
      (node (ref "DZ2") (pin "1") (pinfunction "1_1") (pintype "passive"))
      (node (ref "P2") (pin "4") (pinfunction "4_4") (pintype "passive"))
      (node (ref "Q1") (pin "2") (pinfunction "D_2") (pintype "passive"))
    )
    (net (code "2") (name "/A_LIMT") (class "Default")
      (node (ref "U4") (pin "28") (pinfunction "PB15_28") (pintype "bidirectional"))
    )
    (net (code "3") (name "/BOOT0") (class "Default")
      (node (ref "R102") (pin "2") (pinfunction "2_2") (pintype "passive"))
      (node (ref "U4") (pin "44") (pinfunction "BOOT0_44") (pintype "input"))
    )
    (net (code "4") (name "/EXIO") (class "Default")
      (node (ref "R91") (pin "1") (pinfunction "1_1") (pintype "passive"))
      (node (ref "U4") (pin "46") (pinfunction "PB9_46") (pintype "bidirectional"))
    )
    (net (code "5") (name "/HOLD") (class "Default")
      (node (ref "R65") (pin "1") (pinfunction "1_1") (pintype "passive"))
      (node (ref "U4") (pin "39") (pinfunction "PB3/JTDO_39") (pintype "bidirectional"))
    )
    (net (code "6") (name "/MA_DIR") (class "Default")
      (node (ref "U4") (pin "11") (pinfunction "PA1_11") (pintype "bidirectional"))
    )
    (net (code "7") (name "/MA_STEP") (class "Default")
      (node (ref "U4") (pin "10") (pinfunction "PA0-WKUP_10") (pintype "bidirectional"))
    )
    (net (code "8") (name "/MOTOR_EN") (class "Default")
      (node (ref "R103") (pin "1") (pinfunction "1_1") (pintype "passive"))
      (node (ref "U10") (pin "2") (pinfunction "~{ENABLE}_2") (pintype "passive"))
      (node (ref "U11") (pin "2") (pinfunction "~{ENABLE}_2") (pintype "passive"))
      (node (ref "U4") (pin "18") (pinfunction "PB0_18") (pintype "bidirectional"))
      (node (ref "U8") (pin "2") (pinfunction "~{ENABLE}_2") (pintype "passive"))
      (node (ref "U9") (pin "2") (pinfunction "~{ENABLE}_2") (pintype "passive"))
    )
    (net (code "9") (name "/MS1") (class "Default")
      (node (ref "P30") (pin "1") (pinfunction "1_1") (pintype "passive"))
      (node (ref "R49") (pin "1") (pinfunction "1_1") (pintype "passive"))
      (node (ref "U10") (pin "9") (pinfunction "MS1_9") (pintype "passive"))
      (node (ref "U11") (pin "9") (pinfunction "MS1_9") (pintype "passive"))
      (node (ref "U8") (pin "9") (pinfunction "MS1_9") (pintype "passive"))
      (node (ref "U9") (pin "9") (pinfunction "MS1_9") (pintype "passive"))
    )
    (net (code "10") (name "/MS2") (class "Default")
      (node (ref "P30") (pin "3") (pinfunction "3_3") (pintype "passive"))
      (node (ref "R50") (pin "1") (pinfunction "1_1") (pintype "passive"))
      (node (ref "U10") (pin "10") (pinfunction "MS2_10") (pintype "passive"))
      (node (ref "U11") (pin "10") (pinfunction "MS2_10") (pintype "passive"))
      (node (ref "U8") (pin "10") (pinfunction "MS2_10") (pintype "passive"))
      (node (ref "U9") (pin "10") (pinfunction "MS2_10") (pintype "passive"))
    )
    (net (code "11") (name "/MS3") (class "Default")
      (node (ref "P30") (pin "5") (pinfunction "5_5") (pintype "passive"))
      (node (ref "R51") (pin "1") (pinfunction "1_1") (pintype "passive"))
      (node (ref "U10") (pin "11") (pinfunction "MS3_11") (pintype "passive"))
      (node (ref "U11") (pin "11") (pinfunction "MS3_11") (pintype "passive"))
      (node (ref "U8") (pin "11") (pinfunction "MS3_11") (pintype "passive"))
      (node (ref "U9") (pin "11") (pinfunction "MS3_11") (pintype "passive"))
    )
    (net (code "12") (name "/MX_1A") (class "Default")
      (node (ref "P19") (pin "3") (pinfunction "3_3") (pintype "passive"))
      (node (ref "U8") (pin "24") (pinfunction "OUT1A_24") (pintype "passive"))
    )
    (net (code "13") (name "/MX_1B") (class "Default")
      (node (ref "P19") (pin "4") (pinfunction "4_4") (pintype "passive"))
      (node (ref "U8") (pin "21") (pinfunction "OUT1B_21") (pintype "passive"))
    )
    (net (code "14") (name "/MX_2A") (class "Default")
      (node (ref "P19") (pin "2") (pinfunction "2_2") (pintype "passive"))
      (node (ref "U8") (pin "26") (pinfunction "OUT2A_26") (pintype "passive"))
    )
    (net (code "15") (name "/MX_2B") (class "Default")
      (node (ref "P19") (pin "1") (pinfunction "1_1") (pintype "passive"))
      (node (ref "U8") (pin "1") (pinfunction "OUT2B_1") (pintype "passive"))
    )
    (net (code "16") (name "/MX_DIR") (class "Default")
      (node (ref "J7") (pin "4") (pinfunction "4_4") (pintype "passive"))
      (node (ref "U4") (pin "17") (pinfunction "PA7_17") (pintype "bidirectional"))
      (node (ref "U8") (pin "19") (pinfunction "DIR_19") (pintype "passive"))
    )
    (net (code "17") (name "/MX_STEP") (class "Default")
      (node (ref "J7") (pin "2") (pinfunction "2_2") (pintype "passive"))
      (node (ref "U4") (pin "16") (pinfunction "PA6_16") (pintype "bidirectional"))
      (node (ref "U8") (pin "16") (pinfunction "STEP_16") (pintype "passive"))
    )
    (net (code "18") (name "/MY1_1A") (class "Default")
      (node (ref "P20") (pin "3") (pinfunction "3_3") (pintype "passive"))
      (node (ref "U9") (pin "24") (pinfunction "OUT1A_24") (pintype "passive"))
    )
    (net (code "19") (name "/MY1_1B") (class "Default")
      (node (ref "P20") (pin "4") (pinfunction "4_4") (pintype "passive"))
      (node (ref "U9") (pin "21") (pinfunction "OUT1B_21") (pintype "passive"))
    )
    (net (code "20") (name "/MY1_2A") (class "Default")
      (node (ref "P20") (pin "2") (pinfunction "2_2") (pintype "passive"))
      (node (ref "U9") (pin "26") (pinfunction "OUT2A_26") (pintype "passive"))
    )
    (net (code "21") (name "/MY1_2B") (class "Default")
      (node (ref "P20") (pin "1") (pinfunction "1_1") (pintype "passive"))
      (node (ref "U9") (pin "1") (pinfunction "OUT2B_1") (pintype "passive"))
    )
    (net (code "22") (name "/MY2_1A") (class "Default")
      (node (ref "P21") (pin "2") (pinfunction "2_2") (pintype "passive"))
      (node (ref "U10") (pin "24") (pinfunction "OUT1A_24") (pintype "passive"))
    )
    (net (code "23") (name "/MY2_1B") (class "Default")
      (node (ref "P21") (pin "1") (pinfunction "1_1") (pintype "passive"))
      (node (ref "U10") (pin "21") (pinfunction "OUT1B_21") (pintype "passive"))
    )
    (net (code "24") (name "/MY2_2A") (class "Default")
      (node (ref "P21") (pin "3") (pinfunction "3_3") (pintype "passive"))
      (node (ref "U10") (pin "26") (pinfunction "OUT2A_26") (pintype "passive"))
    )
    (net (code "25") (name "/MY2_2B") (class "Default")
      (node (ref "P21") (pin "4") (pinfunction "4_4") (pintype "passive"))
      (node (ref "U10") (pin "1") (pinfunction "OUT2B_1") (pintype "passive"))
    )
    (net (code "26") (name "/MY_DIR") (class "Default")
      (node (ref "J8") (pin "4") (pinfunction "4_4") (pintype "passive"))
      (node (ref "J9") (pin "4") (pinfunction "4_4") (pintype "passive"))
      (node (ref "U10") (pin "19") (pinfunction "DIR_19") (pintype "passive"))
      (node (ref "U4") (pin "15") (pinfunction "PA5_15") (pintype "bidirectional"))
      (node (ref "U9") (pin "19") (pinfunction "DIR_19") (pintype "passive"))
    )
    (net (code "27") (name "/MY_STEP") (class "Default")
      (node (ref "J8") (pin "2") (pinfunction "2_2") (pintype "passive"))
      (node (ref "J9") (pin "2") (pinfunction "2_2") (pintype "passive"))
      (node (ref "U10") (pin "16") (pinfunction "STEP_16") (pintype "passive"))
      (node (ref "U4") (pin "14") (pinfunction "PA4_14") (pintype "bidirectional"))
      (node (ref "U9") (pin "16") (pinfunction "STEP_16") (pintype "passive"))
    )
    (net (code "28") (name "/MZ_1A") (class "Default")
      (node (ref "P22") (pin "2") (pinfunction "2_2") (pintype "passive"))
      (node (ref "U11") (pin "24") (pinfunction "OUT1A_24") (pintype "passive"))
    )
    (net (code "29") (name "/MZ_1B") (class "Default")
      (node (ref "P22") (pin "1") (pinfunction "1_1") (pintype "passive"))
      (node (ref "U11") (pin "21") (pinfunction "OUT1B_21") (pintype "passive"))
    )
    (net (code "30") (name "/MZ_2A") (class "Default")
      (node (ref "P22") (pin "3") (pinfunction "3_3") (pintype "passive"))
      (node (ref "U11") (pin "26") (pinfunction "OUT2A_26") (pintype "passive"))
    )
    (net (code "31") (name "/MZ_2B") (class "Default")
      (node (ref "P22") (pin "4") (pinfunction "4_4") (pintype "passive"))
      (node (ref "U11") (pin "1") (pinfunction "OUT2B_1") (pintype "passive"))
    )
    (net (code "32") (name "/MZ_DIR") (class "Default")
      (node (ref "J6") (pin "4") (pinfunction "4_4") (pintype "passive"))
      (node (ref "U11") (pin "19") (pinfunction "DIR_19") (pintype "passive"))
      (node (ref "U4") (pin "13") (pinfunction "PA3_13") (pintype "bidirectional"))
    )
    (net (code "33") (name "/MZ_STEP") (class "Default")
      (node (ref "J6") (pin "2") (pinfunction "2_2") (pintype "passive"))
      (node (ref "U11") (pin "16") (pinfunction "STEP_16") (pintype "passive"))
      (node (ref "U4") (pin "12") (pinfunction "PA2_12") (pintype "bidirectional"))
    )
    (net (code "34") (name "/PROBE") (class "Default")
      (node (ref "R63") (pin "1") (pinfunction "1_1") (pintype "passive"))
      (node (ref "U4") (pin "41") (pinfunction "PB5_41") (pintype "bidirectional"))
    )
    (net (code "35") (name "/PWM") (class "Default")
      (node (ref "P14") (pin "3") (pinfunction "3_3") (pintype "passive"))
      (node (ref "P16") (pin "3") (pinfunction "3_3") (pintype "passive"))
      (node (ref "P25") (pin "2") (pintype "passive"))
      (node (ref "R59") (pin "2") (pinfunction "2_2") (pintype "passive"))
    )
    (net (code "36") (name "/RST") (class "Default")
      (node (ref "C27") (pin "2") (pinfunction "2_2") (pintype "passive"))
      (node (ref "K2") (pin "1") (pinfunction "1_1") (pintype "passive"))
      (node (ref "P18") (pin "5") (pinfunction "5_5") (pintype "passive"))
      (node (ref "P5") (pin "1") (pintype "passive"))
      (node (ref "R72") (pin "2") (pinfunction "2_2") (pintype "passive"))
      (node (ref "U4") (pin "42") (pinfunction "PB6_42") (pintype "bidirectional"))
    )
    (net (code "37") (name "/RUN") (class "Default")
      (node (ref "R64") (pin "1") (pinfunction "1_1") (pintype "passive"))
      (node (ref "U4") (pin "40") (pinfunction "PB4/JNTRST_40") (pintype "bidirectional"))
    )
    (net (code "38") (name "/RXD") (class "Default")
      (node (ref "R15") (pin "2") (pinfunction "2_2") (pintype "passive"))
      (node (ref "R25") (pin "1") (pinfunction "1_1") (pintype "passive"))
      (node (ref "U4") (pin "31") (pinfunction "PA10_31") (pintype "bidirectional"))
    )
    (net (code "39") (name "/SPINDLE_PWM") (class "Default")
      (node (ref "R70") (pin "2") (pinfunction "2_2") (pintype "passive"))
      (node (ref "U15") (pin "2") (pinfunction "A_2") (pintype "passive"))
      (node (ref "U16") (pin "2") (pinfunction "A_2") (pintype "passive"))
      (node (ref "U4") (pin "29") (pinfunction "PA8_29") (pintype "bidirectional"))
    )
    (net (code "40") (name "/SWCLK") (class "Default")
      (node (ref "P50") (pin "3") (pinfunction "3_3") (pintype "passive"))
      (node (ref "U4") (pin "37") (pinfunction "PA14/JTCK/SWCLK_37") (pintype "bidirectional"))
    )
    (net (code "41") (name "/SWDIO") (class "Default")
      (node (ref "P50") (pin "4") (pinfunction "4_4") (pintype "passive"))
      (node (ref "U4") (pin "34") (pinfunction "PA13/JTMS/SWDIO_34") (pintype "bidirectional"))
    )
    (net (code "42") (name "/TXD") (class "Default")
      (node (ref "R16") (pin "2") (pinfunction "2_2") (pintype "passive"))
      (node (ref "R22") (pin "1") (pinfunction "1_1") (pintype "passive"))
      (node (ref "U4") (pin "30") (pinfunction "PA9_30") (pintype "bidirectional"))
    )
    (net (code "43") (name "/USB_DM") (class "Default")
      (node (ref "P10") (pin "A7") (pinfunction "D-_A7") (pintype "passive"))
      (node (ref "P10") (pin "B7") (pinfunction "D-_B7") (pintype "passive"))
      (node (ref "U6") (pin "6") (pinfunction "6_6") (pintype "passive"))
    )
    (net (code "44") (name "/USB_DP") (class "Default")
      (node (ref "P10") (pin "A6") (pinfunction "D+_A6") (pintype "passive"))
      (node (ref "P10") (pin "B6") (pinfunction "D+_B6") (pintype "passive"))
      (node (ref "R73") (pin "2") (pinfunction "2_2") (pintype "passive"))
      (node (ref "U6") (pin "5") (pinfunction "5_5") (pintype "passive"))
    )
    (net (code "45") (name "/XTAL1") (class "Default")
      (node (ref "C22") (pin "1") (pinfunction "1_1") (pintype "passive"))
      (node (ref "U4") (pin "5") (pinfunction "OSC_IN/PD0_5") (pintype "input"))
      (node (ref "Y2") (pin "1") (pinfunction "OSC1_1") (pintype "passive"))
    )
    (net (code "46") (name "/XTAL2") (class "Default")
      (node (ref "C21") (pin "1") (pinfunction "1_1") (pintype "passive"))
      (node (ref "U4") (pin "6") (pinfunction "OSC_OUT/PD1_6") (pintype "output"))
      (node (ref "Y2") (pin "2") (pinfunction "OSC2_2") (pintype "passive"))
    )
    (net (code "47") (name "/X_LIMT") (class "Default")
      (node (ref "R60") (pin "1") (pinfunction "1_1") (pintype "passive"))
      (node (ref "U4") (pin "25") (pinfunction "PB12_25") (pintype "bidirectional"))
    )
    (net (code "48") (name "/Y_LIMT") (class "Default")
      (node (ref "R61") (pin "1") (pinfunction "1_1") (pintype "passive"))
      (node (ref "U4") (pin "26") (pinfunction "PB13_26") (pintype "bidirectional"))
    )
    (net (code "49") (name "/Z_LIMT") (class "Default")
      (node (ref "R62") (pin "1") (pinfunction "1_1") (pintype "passive"))
      (node (ref "U4") (pin "27") (pinfunction "PB14_27") (pintype "bidirectional"))
    )
    (net (code "50") (name "/nRST") (class "Default")
      (node (ref "C102") (pin "2") (pinfunction "2_2") (pintype "passive"))
      (node (ref "R104") (pin "2") (pinfunction "2_2") (pintype "passive"))
      (node (ref "U4") (pin "7") (pinfunction "NRST_7") (pintype "bidirectional"))
    )
    (net (code "51") (name "3V3") (class "Default")
      (node (ref "C106") (pin "2") (pinfunction "2_2") (pintype "passive"))
      (node (ref "C107") (pin "2") (pinfunction "2_2") (pintype "passive"))
      (node (ref "C108") (pin "2") (pinfunction "2_2") (pintype "passive"))
      (node (ref "C80") (pin "1") (pintype "passive"))
      (node (ref "C81") (pin "2") (pinfunction "2_2") (pintype "passive"))
      (node (ref "P50") (pin "2") (pinfunction "2_2") (pintype "passive"))
      (node (ref "R103") (pin "2") (pinfunction "2_2") (pintype "passive"))
      (node (ref "R104") (pin "1") (pinfunction "1_1") (pintype "passive"))
      (node (ref "R11") (pin "2") (pinfunction "2_2") (pintype "passive"))
      (node (ref "R14") (pin "2") (pinfunction "2_2") (pintype "passive"))
      (node (ref "R19") (pin "2") (pinfunction "2_2") (pintype "passive"))
      (node (ref "R3") (pin "1") (pinfunction "1_1") (pintype "passive"))
      (node (ref "R66") (pin "2") (pinfunction "2_2") (pintype "passive"))
      (node (ref "R67") (pin "2") (pinfunction "2_2") (pintype "passive"))
      (node (ref "R68") (pin "2") (pinfunction "2_2") (pintype "passive"))
      (node (ref "R71") (pin "2") (pinfunction "2_2") (pintype "passive"))
      (node (ref "R72") (pin "1") (pinfunction "1_1") (pintype "passive"))
      (node (ref "R90") (pin "2") (pinfunction "2_2") (pintype "passive"))
      (node (ref "U4") (pin "24") (pinfunction "VDD_1_24") (pintype "power_in"))
      (node (ref "U4") (pin "36") (pinfunction "VDD_2_36") (pintype "power_in"))
      (node (ref "U4") (pin "48") (pinfunction "VDD_3_48") (pintype "power_in"))
      (node (ref "U4") (pin "9") (pinfunction "VDDA_9") (pintype "power_in"))
      (node (ref "U5") (pin "2") (pinfunction "OUT_2") (pintype "power_in"))
      (node (ref "U5") (pin "4") (pinfunction "=_4") (pintype "power_in"))
    )
    (net (code "52") (name "12V") (class "Default")
      (node (ref "C15") (pin "1") (pintype "passive"))
      (node (ref "C16") (pin "2") (pinfunction "2_2") (pintype "passive"))
      (node (ref "C24") (pin "1") (pintype "passive"))
      (node (ref "C5") (pin "1") (pintype "passive"))
      (node (ref "C52") (pin "2") (pinfunction "2_2") (pintype "passive"))
      (node (ref "C56") (pin "2") (pinfunction "2_2") (pintype "passive"))
      (node (ref "L1") (pin "2") (pinfunction "2_2") (pintype "passive"))
      (node (ref "P14") (pin "1") (pinfunction "1_1") (pintype "passive"))
      (node (ref "P24") (pin "2") (pintype "passive"))
      (node (ref "R1") (pin "2") (pinfunction "2_2") (pintype "passive"))
      (node (ref "R27") (pin "2") (pinfunction "2_2") (pintype "passive"))
      (node (ref "R77") (pin "2") (pinfunction "2_2") (pintype "passive"))
      (node (ref "R78") (pin "2") (pinfunction "2_2") (pintype "passive"))
      (node (ref "U1") (pin "1") (pinfunction "VIN_1") (pintype "passive"))
    )
    (net (code "53") (name "24V") (class "Default")
      (node (ref "C12") (pin "1") (pinfunction "1_1") (pintype "passive"))
      (node (ref "C13") (pin "1") (pintype "passive"))
      (node (ref "C30") (pin "1") (pinfunction "1_1") (pintype "passive"))
      (node (ref "C31") (pin "1") (pinfunction "1_1") (pintype "passive"))
      (node (ref "C32") (pin "1") (pinfunction "1_1") (pintype "passive"))
      (node (ref "C33") (pin "1") (pinfunction "1_1") (pintype "passive"))
      (node (ref "C34") (pin "1") (pintype "passive"))
      (node (ref "C35") (pin "1") (pintype "passive"))
      (node (ref "C36") (pin "1") (pintype "passive"))
      (node (ref "C37") (pin "1") (pintype "passive"))
      (node (ref "C4") (pin "2") (pinfunction "2_2") (pintype "passive"))
      (node (ref "C42") (pin "2") (pinfunction "2_2") (pintype "passive"))
      (node (ref "C43") (pin "2") (pinfunction "2_2") (pintype "passive"))
      (node (ref "C44") (pin "2") (pinfunction "2_2") (pintype "passive"))
      (node (ref "C45") (pin "2") (pinfunction "2_2") (pintype "passive"))
      (node (ref "C70") (pin "1") (pinfunction "1_1") (pintype "passive"))
      (node (ref "D7") (pin "2") (pinfunction "2_2") (pintype "passive"))
      (node (ref "DZ1") (pin "2") (pinfunction "2_2") (pintype "passive"))
      (node (ref "P1") (pin "1") (pinfunction "1_1") (pintype "passive"))
      (node (ref "P16") (pin "1") (pinfunction "1_1") (pintype "passive"))
      (node (ref "P17") (pin "1") (pintype "passive"))
      (node (ref "P27") (pin "1") (pintype "passive"))
      (node (ref "R58") (pin "1") (pinfunction "1_1") (pintype "passive"))
      (node (ref "U10") (pin "22") (pinfunction "VBB1_22") (pintype "passive"))
      (node (ref "U10") (pin "28") (pinfunction "VBB2_28") (pintype "passive"))
      (node (ref "U11") (pin "22") (pinfunction "VBB1_22") (pintype "passive"))
      (node (ref "U11") (pin "28") (pinfunction "VBB2_28") (pintype "passive"))
      (node (ref "U3") (pin "5") (pinfunction "VIN_5") (pintype "passive"))
      (node (ref "U8") (pin "22") (pinfunction "VBB1_22") (pintype "passive"))
      (node (ref "U8") (pin "28") (pinfunction "VBB2_28") (pintype "passive"))
      (node (ref "U9") (pin "22") (pinfunction "VBB1_22") (pintype "passive"))
      (node (ref "U9") (pin "28") (pinfunction "VBB2_28") (pintype "passive"))
    )
    (net (code "54") (name "48V1") (class "Default")
      (node (ref "C1") (pin "1") (pintype "passive"))
      (node (ref "C2") (pin "1") (pintype "passive"))
      (node (ref "D11") (pin "2") (pinfunction "2_2") (pintype "passive"))
      (node (ref "D18") (pin "2") (pinfunction "2_2") (pintype "passive"))
      (node (ref "R4") (pin "2") (pinfunction "2_2") (pintype "passive"))
      (node (ref "U2") (pin "1") (pinfunction "IN_1") (pintype "power_in"))
    )
    (net (code "55") (name "48V_IN") (class "Default")
      (node (ref "D11") (pin "1") (pinfunction "1_1") (pintype "passive"))
      (node (ref "D18") (pin "1") (pinfunction "1_1") (pintype "passive"))
      (node (ref "DZ2") (pin "2") (pinfunction "2_2") (pintype "passive"))
      (node (ref "P2") (pin "1") (pinfunction "1_1") (pintype "passive"))
      (node (ref "P2") (pin "3") (pinfunction "3_3") (pintype "passive"))
      (node (ref "R21") (pin "1") (pinfunction "1_1") (pintype "passive"))
    )
    (net (code "56") (name "GND") (class "Default")
      (node (ref "C1") (pin "2") (pintype "passive"))
      (node (ref "C10") (pin "2") (pintype "passive"))
      (node (ref "C102") (pin "1") (pinfunction "1_1") (pintype "passive"))
      (node (ref "C106") (pin "1") (pinfunction "1_1") (pintype "passive"))
      (node (ref "C107") (pin "1") (pinfunction "1_1") (pintype "passive"))
      (node (ref "C108") (pin "1") (pinfunction "1_1") (pintype "passive"))
      (node (ref "C12") (pin "2") (pinfunction "2_2") (pintype "passive"))
      (node (ref "C13") (pin "2") (pintype "passive"))
      (node (ref "C14") (pin "1") (pinfunction "1_1") (pintype "passive"))
      (node (ref "C15") (pin "2") (pintype "passive"))
      (node (ref "C16") (pin "1") (pinfunction "1_1") (pintype "passive"))
      (node (ref "C17") (pin "1") (pinfunction "1_1") (pintype "passive"))
      (node (ref "C18") (pin "1") (pinfunction "1_1") (pintype "passive"))
      (node (ref "C19") (pin "1") (pinfunction "1_1") (pintype "passive"))
      (node (ref "C2") (pin "2") (pintype "passive"))
      (node (ref "C20") (pin "1") (pinfunction "1_1") (pintype "passive"))
      (node (ref "C21") (pin "2") (pinfunction "2_2") (pintype "passive"))
      (node (ref "C22") (pin "2") (pinfunction "2_2") (pintype "passive"))
      (node (ref "C23") (pin "2") (pinfunction "2_2") (pintype "passive"))
      (node (ref "C24") (pin "2") (pintype "passive"))
      (node (ref "C25") (pin "1") (pinfunction "1_1") (pintype "passive"))
      (node (ref "C26") (pin "1") (pinfunction "1_1") (pintype "passive"))
      (node (ref "C30") (pin "2") (pinfunction "2_2") (pintype "passive"))
      (node (ref "C31") (pin "2") (pinfunction "2_2") (pintype "passive"))
      (node (ref "C32") (pin "2") (pinfunction "2_2") (pintype "passive"))
      (node (ref "C33") (pin "2") (pinfunction "2_2") (pintype "passive"))
      (node (ref "C34") (pin "2") (pintype "passive"))
      (node (ref "C35") (pin "2") (pintype "passive"))
      (node (ref "C36") (pin "2") (pintype "passive"))
      (node (ref "C37") (pin "2") (pintype "passive"))
      (node (ref "C46") (pin "2") (pinfunction "2_2") (pintype "passive"))
      (node (ref "C47") (pin "2") (pinfunction "2_2") (pintype "passive"))
      (node (ref "C48") (pin "2") (pinfunction "2_2") (pintype "passive"))
      (node (ref "C49") (pin "2") (pinfunction "2_2") (pintype "passive"))
      (node (ref "C5") (pin "2") (pintype "passive"))
      (node (ref "C52") (pin "1") (pinfunction "1_1") (pintype "passive"))
      (node (ref "C54") (pin "2") (pinfunction "2_2") (pintype "passive"))
      (node (ref "C55") (pin "2") (pinfunction "2_2") (pintype "passive"))
      (node (ref "C60") (pin "1") (pinfunction "1_1") (pintype "passive"))
      (node (ref "C61") (pin "1") (pinfunction "1_1") (pintype "passive"))
      (node (ref "C62") (pin "1") (pinfunction "1_1") (pintype "passive"))
      (node (ref "C7") (pin "2") (pintype "passive"))
      (node (ref "C70") (pin "2") (pinfunction "2_2") (pintype "passive"))
      (node (ref "C80") (pin "2") (pintype "passive"))
      (node (ref "C81") (pin "1") (pinfunction "1_1") (pintype "passive"))
      (node (ref "C9") (pin "1") (pinfunction "1_1") (pintype "passive"))
      (node (ref "D10") (pin "2") (pinfunction "2_2") (pintype "passive"))
      (node (ref "D17") (pin "1") (pinfunction "1_1") (pintype "passive"))
      (node (ref "D4") (pin "2") (pinfunction "2_2") (pintype "passive"))
      (node (ref "D5") (pin "1") (pinfunction "1_1") (pintype "passive"))
      (node (ref "D6") (pin "1") (pinfunction "1_1") (pintype "passive"))
      (node (ref "DZ4") (pin "1") (pinfunction "1_1") (pintype "passive"))
      (node (ref "K1") (pin "2") (pinfunction "2_2") (pintype "passive"))
      (node (ref "K2") (pin "2") (pinfunction "2_2") (pintype "passive"))
      (node (ref "P10") (pin "1") (pinfunction "EP_1") (pintype "passive"))
      (node (ref "P10") (pin "2") (pinfunction "EP_2") (pintype "passive"))
      (node (ref "P10") (pin "3") (pinfunction "EP_3") (pintype "passive"))
      (node (ref "P10") (pin "4") (pinfunction "EP_4") (pintype "passive"))
      (node (ref "P10") (pin "A1") (pinfunction "GND_A1") (pintype "passive"))
      (node (ref "P10") (pin "A12") (pinfunction "GND_A12") (pintype "passive"))
      (node (ref "P10") (pin "B1") (pinfunction "GND_B1") (pintype "passive"))
      (node (ref "P10") (pin "B12") (pinfunction "GND_B12") (pintype "passive"))
      (node (ref "P11") (pin "2") (pinfunction "2_2") (pintype "passive"))
      (node (ref "P12") (pin "2") (pinfunction "2_2") (pintype "passive"))
      (node (ref "P13") (pin "2") (pintype "passive"))
      (node (ref "P14") (pin "2") (pinfunction "2_2") (pintype "passive"))
      (node (ref "P16") (pin "2") (pinfunction "2_2") (pintype "passive"))
      (node (ref "P18") (pin "3") (pinfunction "3_3") (pintype "passive"))
      (node (ref "P18") (pin "4") (pinfunction "4_4") (pintype "passive"))
      (node (ref "P23") (pin "2") (pintype "passive"))
      (node (ref "P24") (pin "1") (pintype "passive"))
      (node (ref "P25") (pin "1") (pintype "passive"))
      (node (ref "P27") (pin "2") (pintype "passive"))
      (node (ref "P3") (pin "2") (pinfunction "2_2") (pintype "passive"))
      (node (ref "P4") (pin "2") (pinfunction "2_2") (pintype "passive"))
      (node (ref "P5") (pin "2") (pintype "passive"))
      (node (ref "P50") (pin "1") (pinfunction "1_1") (pintype "passive"))
      (node (ref "P6") (pin "2") (pintype "passive"))
      (node (ref "P7") (pin "2") (pinfunction "2_2") (pintype "passive"))
      (node (ref "P8") (pin "2") (pinfunction "2_2") (pintype "passive"))
      (node (ref "P9") (pin "2") (pintype "passive"))
      (node (ref "Q1") (pin "3") (pinfunction "S_3") (pintype "passive"))
      (node (ref "Q2") (pin "3") (pinfunction "S_3") (pintype "passive"))
      (node (ref "Q3") (pin "3") (pinfunction "E_3") (pintype "passive"))
      (node (ref "R100") (pin "1") (pinfunction "1_1") (pintype "passive"))
      (node (ref "R102") (pin "1") (pinfunction "1_1") (pintype "passive"))
      (node (ref "R29") (pin "2") (pinfunction "2_2") (pintype "passive"))
      (node (ref "R30") (pin "1") (pinfunction "1_1") (pintype "passive"))
      (node (ref "R31") (pin "2") (pinfunction "2_2") (pintype "passive"))
      (node (ref "R32") (pin "1") (pinfunction "1_1") (pintype "passive"))
      (node (ref "R33") (pin "2") (pinfunction "2_2") (pintype "passive"))
      (node (ref "R34") (pin "1") (pinfunction "1_1") (pintype "passive"))
      (node (ref "R35") (pin "2") (pinfunction "2_2") (pintype "passive"))
      (node (ref "R36") (pin "1") (pinfunction "1_1") (pintype "passive"))
      (node (ref "R41") (pin "1") (pinfunction "A_1") (pintype "passive"))
      (node (ref "R42") (pin "1") (pinfunction "A_1") (pintype "passive"))
      (node (ref "R43") (pin "1") (pinfunction "A_1") (pintype "passive"))
      (node (ref "R44") (pin "1") (pinfunction "A_1") (pintype "passive"))
      (node (ref "R49") (pin "2") (pinfunction "2_2") (pintype "passive"))
      (node (ref "R50") (pin "2") (pinfunction "2_2") (pintype "passive"))
      (node (ref "R51") (pin "2") (pinfunction "2_2") (pintype "passive"))
      (node (ref "R53") (pin "1") (pinfunction "1_1") (pintype "passive"))
      (node (ref "R54") (pin "1") (pinfunction "1_1") (pintype "passive"))
      (node (ref "R55") (pin "1") (pinfunction "1_1") (pintype "passive"))
      (node (ref "R56") (pin "1") (pinfunction "1_1") (pintype "passive"))
      (node (ref "R57") (pin "2") (pinfunction "2_2") (pintype "passive"))
      (node (ref "R7") (pin "1") (pinfunction "1_1") (pintype "passive"))
      (node (ref "R70") (pin "1") (pinfunction "1_1") (pintype "passive"))
      (node (ref "R75") (pin "2") (pinfunction "2_2") (pintype "passive"))
      (node (ref "R76") (pin "1") (pinfunction "1_1") (pintype "passive"))
      (node (ref "R8") (pin "1") (pinfunction "1_1") (pintype "passive"))
      (node (ref "U1") (pin "2") (pinfunction "GND_2") (pintype "passive"))
      (node (ref "U10") (pin "18") (pinfunction "GND_18") (pintype "passive"))
      (node (ref "U10") (pin "3") (pinfunction "GND_3") (pintype "passive"))
      (node (ref "U11") (pin "18") (pinfunction "GND_18") (pintype "passive"))
      (node (ref "U11") (pin "3") (pinfunction "GND_3") (pintype "passive"))
      (node (ref "U15") (pin "3") (pinfunction "GND_3") (pintype "passive"))
      (node (ref "U16") (pin "3") (pinfunction "GND_3") (pintype "passive"))
      (node (ref "U2") (pin "3") (pinfunction "GND_3") (pintype "power_in"))
      (node (ref "U2") (pin "5") (pinfunction "~{ON}/OFF_5") (pintype "input"))
      (node (ref "U3") (pin "1") (pinfunction "GND_1") (pintype "passive"))
      (node (ref "U4") (pin "20") (pinfunction "PB2/BOOT1_20") (pintype "bidirectional"))
      (node (ref "U4") (pin "23") (pinfunction "VSS_1_23") (pintype "power_in"))
      (node (ref "U4") (pin "35") (pinfunction "VSS_2_35") (pintype "power_in"))
      (node (ref "U4") (pin "47") (pinfunction "VSS_3_47") (pintype "power_in"))
      (node (ref "U4") (pin "8") (pinfunction "VSSA_8") (pintype "power_in"))
      (node (ref "U5") (pin "1") (pinfunction "GND_1") (pintype "power_in"))
      (node (ref "U6") (pin "1") (pinfunction "1_1") (pintype "passive"))
      (node (ref "U8") (pin "18") (pinfunction "GND_18") (pintype "passive"))
      (node (ref "U8") (pin "3") (pinfunction "GND_3") (pintype "passive"))
      (node (ref "U9") (pin "18") (pinfunction "GND_18") (pintype "passive"))
      (node (ref "U9") (pin "3") (pinfunction "GND_3") (pintype "passive"))
    )
    (net (code "57") (name "Net-(C10-Pad1)") (class "Default")
      (node (ref "C10") (pin "1") (pintype "passive"))
      (node (ref "C14") (pin "2") (pinfunction "2_2") (pintype "passive"))
      (node (ref "D7") (pin "1") (pinfunction "1_1") (pintype "passive"))
      (node (ref "L2") (pin "2") (pinfunction "2_2") (pintype "passive"))
      (node (ref "R6") (pin "2") (pinfunction "2_2") (pintype "passive"))
    )
    (net (code "58") (name "Net-(C17-Pad2)") (class "Default")
      (node (ref "C17") (pin "2") (pinfunction "2_2") (pintype "passive"))
      (node (ref "P3") (pin "1") (pinfunction "1_1") (pintype "passive"))
      (node (ref "P4") (pin "1") (pinfunction "1_1") (pintype "passive"))
      (node (ref "R11") (pin "1") (pinfunction "1_1") (pintype "passive"))
      (node (ref "R60") (pin "2") (pinfunction "2_2") (pintype "passive"))
    )
    (net (code "59") (name "Net-(C19-Pad2)") (class "Default")
      (node (ref "C19") (pin "2") (pinfunction "2_2") (pintype "passive"))
      (node (ref "D14") (pin "2") (pinfunction "2_2") (pintype "passive"))
      (node (ref "U6") (pin "16") (pinfunction "16_16") (pintype "passive"))
    )
    (net (code "60") (name "Net-(C20-Pad2)") (class "Default")
      (node (ref "C20") (pin "2") (pinfunction "2_2") (pintype "passive"))
      (node (ref "P7") (pin "1") (pinfunction "1_1") (pintype "passive"))
      (node (ref "P8") (pin "1") (pinfunction "1_1") (pintype "passive"))
      (node (ref "R14") (pin "1") (pinfunction "1_1") (pintype "passive"))
      (node (ref "R61") (pin "2") (pinfunction "2_2") (pintype "passive"))
    )
    (net (code "61") (name "Net-(C23-Pad1)") (class "Default")
      (node (ref "C23") (pin "1") (pinfunction "1_1") (pintype "passive"))
      (node (ref "U6") (pin "4") (pinfunction "4_4") (pintype "passive"))
    )
    (net (code "62") (name "Net-(C25-Pad2)") (class "Default")
      (node (ref "C25") (pin "2") (pinfunction "2_2") (pintype "passive"))
      (node (ref "P23") (pin "1") (pintype "passive"))
      (node (ref "R90") (pin "1") (pinfunction "1_1") (pintype "passive"))
      (node (ref "R91") (pin "2") (pinfunction "2_2") (pintype "passive"))
    )
    (net (code "63") (name "Net-(C26-Pad2)") (class "Default")
      (node (ref "C26") (pin "2") (pinfunction "2_2") (pintype "passive"))
      (node (ref "P11") (pin "1") (pinfunction "1_1") (pintype "passive"))
      (node (ref "P12") (pin "1") (pinfunction "1_1") (pintype "passive"))
      (node (ref "R19") (pin "1") (pinfunction "1_1") (pintype "passive"))
      (node (ref "R62") (pin "2") (pinfunction "2_2") (pintype "passive"))
    )
    (net (code "64") (name "Net-(C27-Pad1)") (class "Default")
      (node (ref "C27") (pin "1") (pinfunction "1_1") (pintype "passive"))
      (node (ref "U6") (pin "13") (pinfunction "13_13") (pintype "passive"))
    )
    (net (code "65") (name "Net-(C60-Pad2)") (class "Default")
      (node (ref "C60") (pin "2") (pinfunction "2_2") (pintype "passive"))
      (node (ref "P6") (pin "1") (pintype "passive"))
      (node (ref "R63") (pin "2") (pinfunction "2_2") (pintype "passive"))
      (node (ref "R66") (pin "1") (pinfunction "1_1") (pintype "passive"))
    )
    (net (code "66") (name "Net-(C61-Pad2)") (class "Default")
      (node (ref "C61") (pin "2") (pinfunction "2_2") (pintype "passive"))
      (node (ref "P9") (pin "1") (pintype "passive"))
      (node (ref "R64") (pin "2") (pinfunction "2_2") (pintype "passive"))
      (node (ref "R67") (pin "1") (pinfunction "1_1") (pintype "passive"))
    )
    (net (code "67") (name "Net-(C62-Pad2)") (class "Default")
      (node (ref "C62") (pin "2") (pinfunction "2_2") (pintype "passive"))
      (node (ref "P13") (pin "1") (pintype "passive"))
      (node (ref "R65") (pin "2") (pinfunction "2_2") (pintype "passive"))
      (node (ref "R68") (pin "1") (pinfunction "1_1") (pintype "passive"))
    )
    (net (code "68") (name "Net-(D4-Pad1)") (class "Default")
      (node (ref "D4") (pin "1") (pinfunction "1_1") (pintype "passive"))
      (node (ref "R3") (pin "2") (pinfunction "2_2") (pintype "passive"))
    )
    (net (code "69") (name "Net-(D10-Pad1)") (class "Default")
      (node (ref "D10") (pin "1") (pinfunction "1_1") (pintype "passive"))
      (node (ref "R4") (pin "1") (pinfunction "1_1") (pintype "passive"))
    )
    (net (code "70") (name "Net-(D12-Pad1)") (class "Default")
      (node (ref "D12") (pin "1") (pinfunction "1_1") (pintype "passive"))
      (node (ref "R71") (pin "1") (pinfunction "1_1") (pintype "passive"))
    )
    (net (code "71") (name "Net-(D13-Pad2)") (class "Default")
      (node (ref "D13") (pin "2") (pinfunction "2_2") (pintype "passive"))
      (node (ref "R76") (pin "2") (pinfunction "2_2") (pintype "passive"))
    )
    (net (code "72") (name "Net-(D15-Pad1)") (class "Default")
      (node (ref "D15") (pin "1") (pinfunction "1_1") (pintype "passive"))
      (node (ref "R21") (pin "2") (pinfunction "2_2") (pintype "passive"))
    )
    (net (code "73") (name "Net-(D16-Pad1)") (class "Default")
      (node (ref "D16") (pin "1") (pinfunction "1_1") (pintype "passive"))
      (node (ref "R58") (pin "2") (pinfunction "2_2") (pintype "passive"))
    )
    (net (code "74") (name "Net-(K1-Pad1)") (class "Default")
      (node (ref "K1") (pin "1") (pinfunction "1_1") (pintype "passive"))
      (node (ref "P1") (pin "2") (pinfunction "2_2") (pintype "passive"))
      (node (ref "P1") (pin "3") (pinfunction "3_3") (pintype "passive"))
      (node (ref "P1") (pin "4") (pinfunction "4_4") (pintype "passive"))
      (node (ref "P1") (pin "5") (pinfunction "5_5") (pintype "passive"))
      (node (ref "P1") (pin "6") (pinfunction "6_6") (pintype "passive"))
      (node (ref "P2") (pin "2") (pinfunction "2_2") (pintype "passive"))
    )
    (net (code "75") (name "Net-(P18-Pad6)") (class "Default")
      (node (ref "P18") (pin "6") (pinfunction "6_6") (pintype "passive"))
      (node (ref "R22") (pin "2") (pinfunction "2_2") (pintype "passive"))
    )
    (net (code "76") (name "Net-(P18-Pad8)") (class "Default")
      (node (ref "P18") (pin "8") (pinfunction "8_8") (pintype "passive"))
      (node (ref "R25") (pin "2") (pinfunction "2_2") (pintype "passive"))
    )
    (net (code "77") (name "Net-(P30-Pad2)") (class "Default")
      (node (ref "P30") (pin "2") (pinfunction "2_2") (pintype "passive"))
      (node (ref "P30") (pin "4") (pinfunction "4_4") (pintype "passive"))
      (node (ref "P30") (pin "6") (pinfunction "6_6") (pintype "passive"))
      (node (ref "R52") (pin "2") (pinfunction "2_2") (pintype "passive"))
    )
    (net (code "78") (name "Net-(Q1-G)") (class "Default")
      (node (ref "DZ4") (pin "2") (pinfunction "2_2") (pintype "passive"))
      (node (ref "Q1") (pin "1") (pinfunction "G_1") (pintype "passive"))
      (node (ref "Q2") (pin "1") (pinfunction "G_1") (pintype "passive"))
      (node (ref "Q3") (pin "2") (pinfunction "C_2") (pintype "passive"))
      (node (ref "R27") (pin "1") (pinfunction "1_1") (pintype "passive"))
      (node (ref "R57") (pin "1") (pinfunction "1_1") (pintype "passive"))
      (node (ref "R77") (pin "1") (pinfunction "1_1") (pintype "passive"))
      (node (ref "R78") (pin "1") (pinfunction "1_1") (pintype "passive"))
    )
    (net (code "79") (name "Net-(Q2-D)") (class "Default")
      (node (ref "D16") (pin "2") (pinfunction "2_2") (pintype "passive"))
      (node (ref "DZ1") (pin "1") (pinfunction "1_1") (pintype "passive"))
      (node (ref "P17") (pin "2") (pintype "passive"))
      (node (ref "Q2") (pin "2") (pinfunction "D_2") (pintype "passive"))
    )
    (net (code "80") (name "Net-(Q3-B)") (class "Default")
      (node (ref "Q3") (pin "1") (pinfunction "B_1") (pintype "passive"))
      (node (ref "R80") (pin "2") (pinfunction "2_2") (pintype "passive"))
      (node (ref "R81") (pin "1") (pinfunction "1_1") (pintype "passive"))
    )
    (net (code "81") (name "Net-(R15-Pad1)") (class "Default")
      (node (ref "R15") (pin "1") (pinfunction "1_1") (pintype "passive"))
      (node (ref "U6") (pin "2") (pinfunction "2_2") (pintype "passive"))
    )
    (net (code "82") (name "Net-(R16-Pad1)") (class "Default")
      (node (ref "R16") (pin "1") (pinfunction "1_1") (pintype "passive"))
      (node (ref "U6") (pin "3") (pinfunction "3_3") (pintype "passive"))
    )
    (net (code "83") (name "Net-(R41-B)") (class "Default")
      (node (ref "R37") (pin "1") (pinfunction "1_1") (pintype "passive"))
      (node (ref "R41") (pin "3") (pinfunction "B_3") (pintype "passive"))
    )
    (net (code "84") (name "Net-(R41-TAP)") (class "Default")
      (node (ref "R41") (pin "2") (pinfunction "TAP_2") (pintype "passive"))
      (node (ref "U8") (pin "17") (pinfunction "REF_17") (pintype "passive"))
    )
    (net (code "85") (name "Net-(R42-B)") (class "Default")
      (node (ref "R38") (pin "1") (pinfunction "1_1") (pintype "passive"))
      (node (ref "R42") (pin "3") (pinfunction "B_3") (pintype "passive"))
    )
    (net (code "86") (name "Net-(R42-TAP)") (class "Default")
      (node (ref "R42") (pin "2") (pinfunction "TAP_2") (pintype "passive"))
      (node (ref "U9") (pin "17") (pinfunction "REF_17") (pintype "passive"))
    )
    (net (code "87") (name "Net-(R43-B)") (class "Default")
      (node (ref "R39") (pin "1") (pinfunction "1_1") (pintype "passive"))
      (node (ref "R43") (pin "3") (pinfunction "B_3") (pintype "passive"))
    )
    (net (code "88") (name "Net-(R43-TAP)") (class "Default")
      (node (ref "R43") (pin "2") (pinfunction "TAP_2") (pintype "passive"))
      (node (ref "U10") (pin "17") (pinfunction "REF_17") (pintype "passive"))
    )
    (net (code "89") (name "Net-(R44-B)") (class "Default")
      (node (ref "R40") (pin "1") (pinfunction "1_1") (pintype "passive"))
      (node (ref "R44") (pin "3") (pinfunction "B_3") (pintype "passive"))
    )
    (net (code "90") (name "Net-(R44-TAP)") (class "Default")
      (node (ref "R44") (pin "2") (pinfunction "TAP_2") (pintype "passive"))
      (node (ref "U11") (pin "17") (pinfunction "REF_17") (pintype "passive"))
    )
    (net (code "91") (name "Net-(U2-FB)") (class "Default")
      (node (ref "R6") (pin "1") (pinfunction "1_1") (pintype "passive"))
      (node (ref "R8") (pin "2") (pinfunction "2_2") (pintype "passive"))
      (node (ref "U2") (pin "4") (pinfunction "FB_4") (pintype "input"))
    )
    (net (code "92") (name "Net-(U2-OUT)") (class "Default")
      (node (ref "D5") (pin "2") (pinfunction "2_2") (pintype "passive"))
      (node (ref "L2") (pin "1") (pinfunction "1_1") (pintype "passive"))
      (node (ref "U2") (pin "2") (pinfunction "OUT_2") (pintype "power_in"))
    )
    (net (code "93") (name "Net-(U3-EN)") (class "Default")
      (node (ref "C4") (pin "1") (pinfunction "1_1") (pintype "passive"))
      (node (ref "U3") (pin "4") (pinfunction "EN_4") (pintype "passive"))
    )
    (net (code "94") (name "Net-(U3-FB)") (class "Default")
      (node (ref "C56") (pin "1") (pinfunction "1_1") (pintype "passive"))
      (node (ref "R1") (pin "1") (pinfunction "1_1") (pintype "passive"))
      (node (ref "R7") (pin "2") (pinfunction "2_2") (pintype "passive"))
      (node (ref "U3") (pin "2") (pinfunction "FB_2") (pintype "passive"))
    )
    (net (code "95") (name "Net-(U3-SW)") (class "Default")
      (node (ref "D6") (pin "2") (pinfunction "2_2") (pintype "passive"))
      (node (ref "L1") (pin "1") (pinfunction "1_1") (pintype "passive"))
      (node (ref "U3") (pin "3") (pinfunction "SW_3") (pintype "passive"))
    )
    (net (code "96") (name "Net-(U4-PA15{slash}JTDI)") (class "Default")
      (node (ref "D12") (pin "2") (pinfunction "2_2") (pintype "passive"))
      (node (ref "U4") (pin "38") (pinfunction "PA15/JTDI_38") (pintype "bidirectional"))
    )
    (net (code "97") (name "Net-(U8-CP1)") (class "Default")
      (node (ref "C38") (pin "1") (pinfunction "1_1") (pintype "passive"))
      (node (ref "U8") (pin "4") (pinfunction "CP1_4") (pintype "passive"))
    )
    (net (code "98") (name "Net-(U8-CP2)") (class "Default")
      (node (ref "C38") (pin "2") (pinfunction "2_2") (pintype "passive"))
      (node (ref "U8") (pin "5") (pinfunction "CP2_5") (pintype "passive"))
    )
    (net (code "99") (name "Net-(U8-SENSE1)") (class "Default")
      (node (ref "R30") (pin "2") (pinfunction "2_2") (pintype "passive"))
      (node (ref "U8") (pin "23") (pinfunction "SENSE1_23") (pintype "passive"))
    )
    (net (code "100") (name "Net-(U8-SENSE2)") (class "Default")
      (node (ref "R29") (pin "1") (pinfunction "1_1") (pintype "passive"))
      (node (ref "U8") (pin "27") (pinfunction "SENSE2_27") (pintype "passive"))
    )
    (net (code "101") (name "Net-(U8-VCP)") (class "Default")
      (node (ref "C42") (pin "1") (pinfunction "1_1") (pintype "passive"))
      (node (ref "U8") (pin "6") (pinfunction "VCP_6") (pintype "passive"))
    )
    (net (code "102") (name "Net-(U8-VREG)") (class "Default")
      (node (ref "C46") (pin "1") (pinfunction "1_1") (pintype "passive"))
      (node (ref "U8") (pin "8") (pinfunction "VREG_8") (pintype "passive"))
    )
    (net (code "103") (name "Net-(U8-~{RESET})") (class "Default")
      (node (ref "R45") (pin "2") (pinfunction "2_2") (pintype "passive"))
      (node (ref "U8") (pin "12") (pinfunction "~{RESET}_12") (pintype "passive"))
      (node (ref "U8") (pin "14") (pinfunction "~{SLEEP}_14") (pintype "passive"))
    )
    (net (code "104") (name "Net-(U8-~{ROSC})") (class "Default")
      (node (ref "R53") (pin "2") (pinfunction "2_2") (pintype "passive"))
      (node (ref "U8") (pin "13") (pinfunction "~{ROSC}_13") (pintype "passive"))
    )
    (net (code "105") (name "Net-(U9-CP1)") (class "Default")
      (node (ref "C39") (pin "1") (pinfunction "1_1") (pintype "passive"))
      (node (ref "U9") (pin "4") (pinfunction "CP1_4") (pintype "passive"))
    )
    (net (code "106") (name "Net-(U9-CP2)") (class "Default")
      (node (ref "C39") (pin "2") (pinfunction "2_2") (pintype "passive"))
      (node (ref "U9") (pin "5") (pinfunction "CP2_5") (pintype "passive"))
    )
    (net (code "107") (name "Net-(U9-SENSE1)") (class "Default")
      (node (ref "R32") (pin "2") (pinfunction "2_2") (pintype "passive"))
      (node (ref "U9") (pin "23") (pinfunction "SENSE1_23") (pintype "passive"))
    )
    (net (code "108") (name "Net-(U9-SENSE2)") (class "Default")
      (node (ref "R31") (pin "1") (pinfunction "1_1") (pintype "passive"))
      (node (ref "U9") (pin "27") (pinfunction "SENSE2_27") (pintype "passive"))
    )
    (net (code "109") (name "Net-(U9-VCP)") (class "Default")
      (node (ref "C43") (pin "1") (pinfunction "1_1") (pintype "passive"))
      (node (ref "U9") (pin "6") (pinfunction "VCP_6") (pintype "passive"))
    )
    (net (code "110") (name "Net-(U9-VREG)") (class "Default")
      (node (ref "C47") (pin "1") (pinfunction "1_1") (pintype "passive"))
      (node (ref "U9") (pin "8") (pinfunction "VREG_8") (pintype "passive"))
    )
    (net (code "111") (name "Net-(U9-~{RESET})") (class "Default")
      (node (ref "R46") (pin "2") (pinfunction "2_2") (pintype "passive"))
      (node (ref "U9") (pin "12") (pinfunction "~{RESET}_12") (pintype "passive"))
      (node (ref "U9") (pin "14") (pinfunction "~{SLEEP}_14") (pintype "passive"))
    )
    (net (code "112") (name "Net-(U9-~{ROSC})") (class "Default")
      (node (ref "R54") (pin "2") (pinfunction "2_2") (pintype "passive"))
      (node (ref "U9") (pin "13") (pinfunction "~{ROSC}_13") (pintype "passive"))
    )
    (net (code "113") (name "Net-(U10-CP1)") (class "Default")
      (node (ref "C40") (pin "1") (pinfunction "1_1") (pintype "passive"))
      (node (ref "U10") (pin "4") (pinfunction "CP1_4") (pintype "passive"))
    )
    (net (code "114") (name "Net-(U10-CP2)") (class "Default")
      (node (ref "C40") (pin "2") (pinfunction "2_2") (pintype "passive"))
      (node (ref "U10") (pin "5") (pinfunction "CP2_5") (pintype "passive"))
    )
    (net (code "115") (name "Net-(U10-SENSE1)") (class "Default")
      (node (ref "R34") (pin "2") (pinfunction "2_2") (pintype "passive"))
      (node (ref "U10") (pin "23") (pinfunction "SENSE1_23") (pintype "passive"))
    )
    (net (code "116") (name "Net-(U10-SENSE2)") (class "Default")
      (node (ref "R33") (pin "1") (pinfunction "1_1") (pintype "passive"))
      (node (ref "U10") (pin "27") (pinfunction "SENSE2_27") (pintype "passive"))
    )
    (net (code "117") (name "Net-(U10-VCP)") (class "Default")
      (node (ref "C44") (pin "1") (pinfunction "1_1") (pintype "passive"))
      (node (ref "U10") (pin "6") (pinfunction "VCP_6") (pintype "passive"))
    )
    (net (code "118") (name "Net-(U10-VREG)") (class "Default")
      (node (ref "C48") (pin "1") (pinfunction "1_1") (pintype "passive"))
      (node (ref "U10") (pin "8") (pinfunction "VREG_8") (pintype "passive"))
    )
    (net (code "119") (name "Net-(U10-~{RESET})") (class "Default")
      (node (ref "R47") (pin "2") (pinfunction "2_2") (pintype "passive"))
      (node (ref "U10") (pin "12") (pinfunction "~{RESET}_12") (pintype "passive"))
      (node (ref "U10") (pin "14") (pinfunction "~{SLEEP}_14") (pintype "passive"))
    )
    (net (code "120") (name "Net-(U10-~{ROSC})") (class "Default")
      (node (ref "R55") (pin "2") (pinfunction "2_2") (pintype "passive"))
      (node (ref "U10") (pin "13") (pinfunction "~{ROSC}_13") (pintype "passive"))
    )
    (net (code "121") (name "Net-(U11-CP1)") (class "Default")
      (node (ref "C41") (pin "1") (pinfunction "1_1") (pintype "passive"))
      (node (ref "U11") (pin "4") (pinfunction "CP1_4") (pintype "passive"))
    )
    (net (code "122") (name "Net-(U11-CP2)") (class "Default")
      (node (ref "C41") (pin "2") (pinfunction "2_2") (pintype "passive"))
      (node (ref "U11") (pin "5") (pinfunction "CP2_5") (pintype "passive"))
    )
    (net (code "123") (name "Net-(U11-SENSE1)") (class "Default")
      (node (ref "R36") (pin "2") (pinfunction "2_2") (pintype "passive"))
      (node (ref "U11") (pin "23") (pinfunction "SENSE1_23") (pintype "passive"))
    )
    (net (code "124") (name "Net-(U11-SENSE2)") (class "Default")
      (node (ref "R35") (pin "1") (pinfunction "1_1") (pintype "passive"))
      (node (ref "U11") (pin "27") (pinfunction "SENSE2_27") (pintype "passive"))
    )
    (net (code "125") (name "Net-(U11-VCP)") (class "Default")
      (node (ref "C45") (pin "1") (pinfunction "1_1") (pintype "passive"))
      (node (ref "U11") (pin "6") (pinfunction "VCP_6") (pintype "passive"))
    )
    (net (code "126") (name "Net-(U11-VREG)") (class "Default")
      (node (ref "C49") (pin "1") (pinfunction "1_1") (pintype "passive"))
      (node (ref "U11") (pin "8") (pinfunction "VREG_8") (pintype "passive"))
    )
    (net (code "127") (name "Net-(U11-~{RESET})") (class "Default")
      (node (ref "R48") (pin "2") (pinfunction "2_2") (pintype "passive"))
      (node (ref "U11") (pin "12") (pinfunction "~{RESET}_12") (pintype "passive"))
      (node (ref "U11") (pin "14") (pinfunction "~{SLEEP}_14") (pintype "passive"))
    )
    (net (code "128") (name "Net-(U11-~{ROSC})") (class "Default")
      (node (ref "R56") (pin "2") (pinfunction "2_2") (pintype "passive"))
      (node (ref "U11") (pin "13") (pinfunction "~{ROSC}_13") (pintype "passive"))
    )
    (net (code "129") (name "Net-(U15-Y)") (class "Default")
      (node (ref "R80") (pin "1") (pinfunction "1_1") (pintype "passive"))
      (node (ref "U15") (pin "4") (pinfunction "Y_4") (pintype "passive"))
    )
    (net (code "130") (name "Net-(U16-Y)") (class "Default")
      (node (ref "R59") (pin "1") (pinfunction "1_1") (pintype "passive"))
      (node (ref "U16") (pin "4") (pinfunction "Y_4") (pintype "passive"))
    )
    (net (code "131") (name "Net-(Y1-OSC1)") (class "Default")
      (node (ref "C55") (pin "1") (pinfunction "1_1") (pintype "passive"))
      (node (ref "U6") (pin "8") (pinfunction "8_8") (pintype "passive"))
      (node (ref "Y1") (pin "1") (pinfunction "OSC1_1") (pintype "passive"))
    )
    (net (code "132") (name "Net-(Y1-OSC2)") (class "Default")
      (node (ref "C54") (pin "1") (pinfunction "1_1") (pintype "passive"))
      (node (ref "U6") (pin "7") (pinfunction "7_7") (pintype "passive"))
      (node (ref "Y1") (pin "2") (pinfunction "OSC2_2") (pintype "passive"))
    )
    (net (code "133") (name "USB-CHK") (class "Default")
      (node (ref "R74") (pin "2") (pinfunction "2_2") (pintype "passive"))
      (node (ref "R75") (pin "1") (pinfunction "1_1") (pintype "passive"))
      (node (ref "U4") (pin "19") (pinfunction "PB1_19") (pintype "bidirectional"))
    )
    (net (code "134") (name "VCC") (class "Default")
      (node (ref "C18") (pin "2") (pinfunction "2_2") (pintype "passive"))
      (node (ref "C7") (pin "1") (pintype "passive"))
      (node (ref "C9") (pin "2") (pinfunction "2_2") (pintype "passive"))
      (node (ref "D9") (pin "2") (pinfunction "2_2") (pintype "passive"))
      (node (ref "J6") (pin "1") (pinfunction "1_1") (pintype "passive"))
      (node (ref "J6") (pin "3") (pinfunction "3_3") (pintype "passive"))
      (node (ref "J7") (pin "1") (pinfunction "1_1") (pintype "passive"))
      (node (ref "J7") (pin "3") (pinfunction "3_3") (pintype "passive"))
      (node (ref "J8") (pin "1") (pinfunction "1_1") (pintype "passive"))
      (node (ref "J8") (pin "3") (pinfunction "3_3") (pintype "passive"))
      (node (ref "J9") (pin "1") (pinfunction "1_1") (pintype "passive"))
      (node (ref "J9") (pin "3") (pinfunction "3_3") (pintype "passive"))
      (node (ref "P11") (pin "3") (pinfunction "3_3") (pintype "passive"))
      (node (ref "P12") (pin "3") (pinfunction "3_3") (pintype "passive"))
      (node (ref "P18") (pin "1") (pinfunction "1_1") (pintype "passive"))
      (node (ref "P18") (pin "2") (pinfunction "2_2") (pintype "passive"))
      (node (ref "P3") (pin "3") (pinfunction "3_3") (pintype "passive"))
      (node (ref "P4") (pin "3") (pinfunction "3_3") (pintype "passive"))
      (node (ref "P7") (pin "3") (pinfunction "3_3") (pintype "passive"))
      (node (ref "P8") (pin "3") (pinfunction "3_3") (pintype "passive"))
      (node (ref "R37") (pin "2") (pinfunction "2_2") (pintype "passive"))
      (node (ref "R38") (pin "2") (pinfunction "2_2") (pintype "passive"))
      (node (ref "R39") (pin "2") (pinfunction "2_2") (pintype "passive"))
      (node (ref "R40") (pin "2") (pinfunction "2_2") (pintype "passive"))
      (node (ref "R45") (pin "1") (pinfunction "1_1") (pintype "passive"))
      (node (ref "R46") (pin "1") (pinfunction "1_1") (pintype "passive"))
      (node (ref "R47") (pin "1") (pinfunction "1_1") (pintype "passive"))
      (node (ref "R48") (pin "1") (pinfunction "1_1") (pintype "passive"))
      (node (ref "R52") (pin "1") (pinfunction "1_1") (pintype "passive"))
      (node (ref "R81") (pin "2") (pinfunction "2_2") (pintype "passive"))
      (node (ref "U1") (pin "3") (pinfunction "VOUT_3") (pintype "passive"))
      (node (ref "U10") (pin "15") (pinfunction "VDD_15") (pintype "passive"))
      (node (ref "U11") (pin "15") (pinfunction "VDD_15") (pintype "passive"))
      (node (ref "U15") (pin "5") (pinfunction "VCC_5") (pintype "passive"))
      (node (ref "U16") (pin "5") (pinfunction "VCC_5") (pintype "passive"))
      (node (ref "U5") (pin "3") (pinfunction "IN_3") (pintype "power_in"))
      (node (ref "U8") (pin "15") (pinfunction "VDD_15") (pintype "passive"))
      (node (ref "U9") (pin "15") (pinfunction "VDD_15") (pintype "passive"))
    )
    (net (code "135") (name "VUSB") (class "Default")
      (node (ref "D13") (pin "1") (pinfunction "1_1") (pintype "passive"))
      (node (ref "D14") (pin "1") (pinfunction "1_1") (pintype "passive"))
      (node (ref "D9") (pin "1") (pinfunction "1_1") (pintype "passive"))
      (node (ref "P10") (pin "A4") (pinfunction "VBUS_A4") (pintype "passive"))
      (node (ref "P10") (pin "A9") (pinfunction "VBUS_A9") (pintype "passive"))
      (node (ref "P10") (pin "B4") (pinfunction "VBUS_B4") (pintype "passive"))
      (node (ref "P10") (pin "B9") (pinfunction "VBUS_B9") (pintype "passive"))
      (node (ref "R100") (pin "2") (pinfunction "2_2") (pintype "passive"))
      (node (ref "R73") (pin "1") (pinfunction "1_1") (pintype "passive"))
      (node (ref "R74") (pin "1") (pinfunction "1_1") (pintype "passive"))
    )
    (net (code "136") (name "unconnected-(P10-CC1-PadA5)") (class "Default")
      (node (ref "P10") (pin "A5") (pinfunction "CC1_A5") (pintype "passive"))
    )
    (net (code "137") (name "unconnected-(P10-CC2-PadB5)") (class "Default")
      (node (ref "P10") (pin "B5") (pinfunction "CC2_B5") (pintype "passive"))
    )
    (net (code "138") (name "unconnected-(P10-SUB1-PadA8)") (class "Default")
      (node (ref "P10") (pin "A8") (pinfunction "SUB1_A8") (pintype "passive"))
    )
    (net (code "139") (name "unconnected-(P10-SUB2-PadB8)") (class "Default")
      (node (ref "P10") (pin "B8") (pinfunction "SUB2_B8") (pintype "passive"))
    )
    (net (code "140") (name "unconnected-(P18-Pad7)") (class "Default")
      (node (ref "P18") (pin "7") (pinfunction "7_7") (pintype "passive"))
    )
    (net (code "141") (name "unconnected-(U4-PA11-Pad32)") (class "Default")
      (node (ref "U4") (pin "32") (pinfunction "PA11_32") (pintype "bidirectional"))
    )
    (net (code "142") (name "unconnected-(U4-PA12-Pad33)") (class "Default")
      (node (ref "U4") (pin "33") (pinfunction "PA12_33") (pintype "bidirectional"))
    )
    (net (code "143") (name "unconnected-(U4-PB7-Pad43)") (class "Default")
      (node (ref "U4") (pin "43") (pinfunction "PB7_43") (pintype "bidirectional"))
    )
    (net (code "144") (name "unconnected-(U4-PB8-Pad45)") (class "Default")
      (node (ref "U4") (pin "45") (pinfunction "PB8_45") (pintype "bidirectional"))
    )
    (net (code "145") (name "unconnected-(U4-PB10-Pad21)") (class "Default")
      (node (ref "U4") (pin "21") (pinfunction "PB10_21") (pintype "bidirectional"))
    )
    (net (code "146") (name "unconnected-(U4-PB11-Pad22)") (class "Default")
      (node (ref "U4") (pin "22") (pinfunction "PB11_22") (pintype "bidirectional"))
    )
    (net (code "147") (name "unconnected-(U4-PC13-TAMPER-RTC-Pad2)") (class "Default")
      (node (ref "U4") (pin "2") (pinfunction "PC13-TAMPER-RTC_2") (pintype "bidirectional"))
    )
    (net (code "148") (name "unconnected-(U4-PC14-OSC32_IN-Pad3)") (class "Default")
      (node (ref "U4") (pin "3") (pinfunction "PC14-OSC32_IN_3") (pintype "bidirectional"))
    )
    (net (code "149") (name "unconnected-(U4-PC15-OSC32_OUT-Pad4)") (class "Default")
      (node (ref "U4") (pin "4") (pinfunction "PC15-OSC32_OUT_4") (pintype "bidirectional"))
    )
    (net (code "150") (name "unconnected-(U4-VBAT-Pad1)") (class "Default")
      (node (ref "U4") (pin "1") (pinfunction "VBAT_1") (pintype "power_in"))
    )
    (net (code "151") (name "unconnected-(U6-Pad9)") (class "Default")
      (node (ref "U6") (pin "9") (pinfunction "9_9") (pintype "passive"))
    )
    (net (code "152") (name "unconnected-(U6-Pad10)") (class "Default")
      (node (ref "U6") (pin "10") (pinfunction "10_10") (pintype "passive"))
    )
    (net (code "153") (name "unconnected-(U6-Pad11)") (class "Default")
      (node (ref "U6") (pin "11") (pinfunction "11_11") (pintype "passive"))
    )
    (net (code "154") (name "unconnected-(U6-Pad12)") (class "Default")
      (node (ref "U6") (pin "12") (pinfunction "12_12") (pintype "passive"))
    )
    (net (code "155") (name "unconnected-(U6-Pad14)") (class "Default")
      (node (ref "U6") (pin "14") (pinfunction "14_14") (pintype "passive"))
    )
    (net (code "156") (name "unconnected-(U6-Pad15)") (class "Default")
      (node (ref "U6") (pin "15") (pinfunction "15_15") (pintype "passive"))
    )
    (net (code "157") (name "unconnected-(U8-NC-Pad7)") (class "Default")
      (node (ref "U8") (pin "7") (pinfunction "NC_7") (pintype "passive"))
    )
    (net (code "158") (name "unconnected-(U8-NC-Pad20)") (class "Default")
      (node (ref "U8") (pin "20") (pinfunction "NC_20") (pintype "passive"))
    )
    (net (code "159") (name "unconnected-(U8-NC-Pad25)") (class "Default")
      (node (ref "U8") (pin "25") (pinfunction "NC_25") (pintype "passive"))
    )
    (net (code "160") (name "unconnected-(U9-NC-Pad7)") (class "Default")
      (node (ref "U9") (pin "7") (pinfunction "NC_7") (pintype "passive"))
    )
    (net (code "161") (name "unconnected-(U9-NC-Pad20)") (class "Default")
      (node (ref "U9") (pin "20") (pinfunction "NC_20") (pintype "passive"))
    )
    (net (code "162") (name "unconnected-(U9-NC-Pad25)") (class "Default")
      (node (ref "U9") (pin "25") (pinfunction "NC_25") (pintype "passive"))
    )
    (net (code "163") (name "unconnected-(U10-NC-Pad7)") (class "Default")
      (node (ref "U10") (pin "7") (pinfunction "NC_7") (pintype "passive"))
    )
    (net (code "164") (name "unconnected-(U10-NC-Pad20)") (class "Default")
      (node (ref "U10") (pin "20") (pinfunction "NC_20") (pintype "passive"))
    )
    (net (code "165") (name "unconnected-(U10-NC-Pad25)") (class "Default")
      (node (ref "U10") (pin "25") (pinfunction "NC_25") (pintype "passive"))
    )
    (net (code "166") (name "unconnected-(U11-NC-Pad7)") (class "Default")
      (node (ref "U11") (pin "7") (pinfunction "NC_7") (pintype "passive"))
    )
    (net (code "167") (name "unconnected-(U11-NC-Pad20)") (class "Default")
      (node (ref "U11") (pin "20") (pinfunction "NC_20") (pintype "passive"))
    )
    (net (code "168") (name "unconnected-(U11-NC-Pad25)") (class "Default")
      (node (ref "U11") (pin "25") (pinfunction "NC_25") (pintype "passive"))
    )
    (net (code "169") (name "unconnected-(U15-NC-Pad1)") (class "Default")
      (node (ref "U15") (pin "1") (pinfunction "NC_1") (pintype "passive"))
    )
    (net (code "170") (name "unconnected-(U16-NC-Pad1)") (class "Default")
      (node (ref "U16") (pin "1") (pinfunction "NC_1") (pintype "passive"))
    )
  )
)
